# Logic_Engine_-_Rear_LED.net
KiCad netlist of a schematic drawn in EAGLE
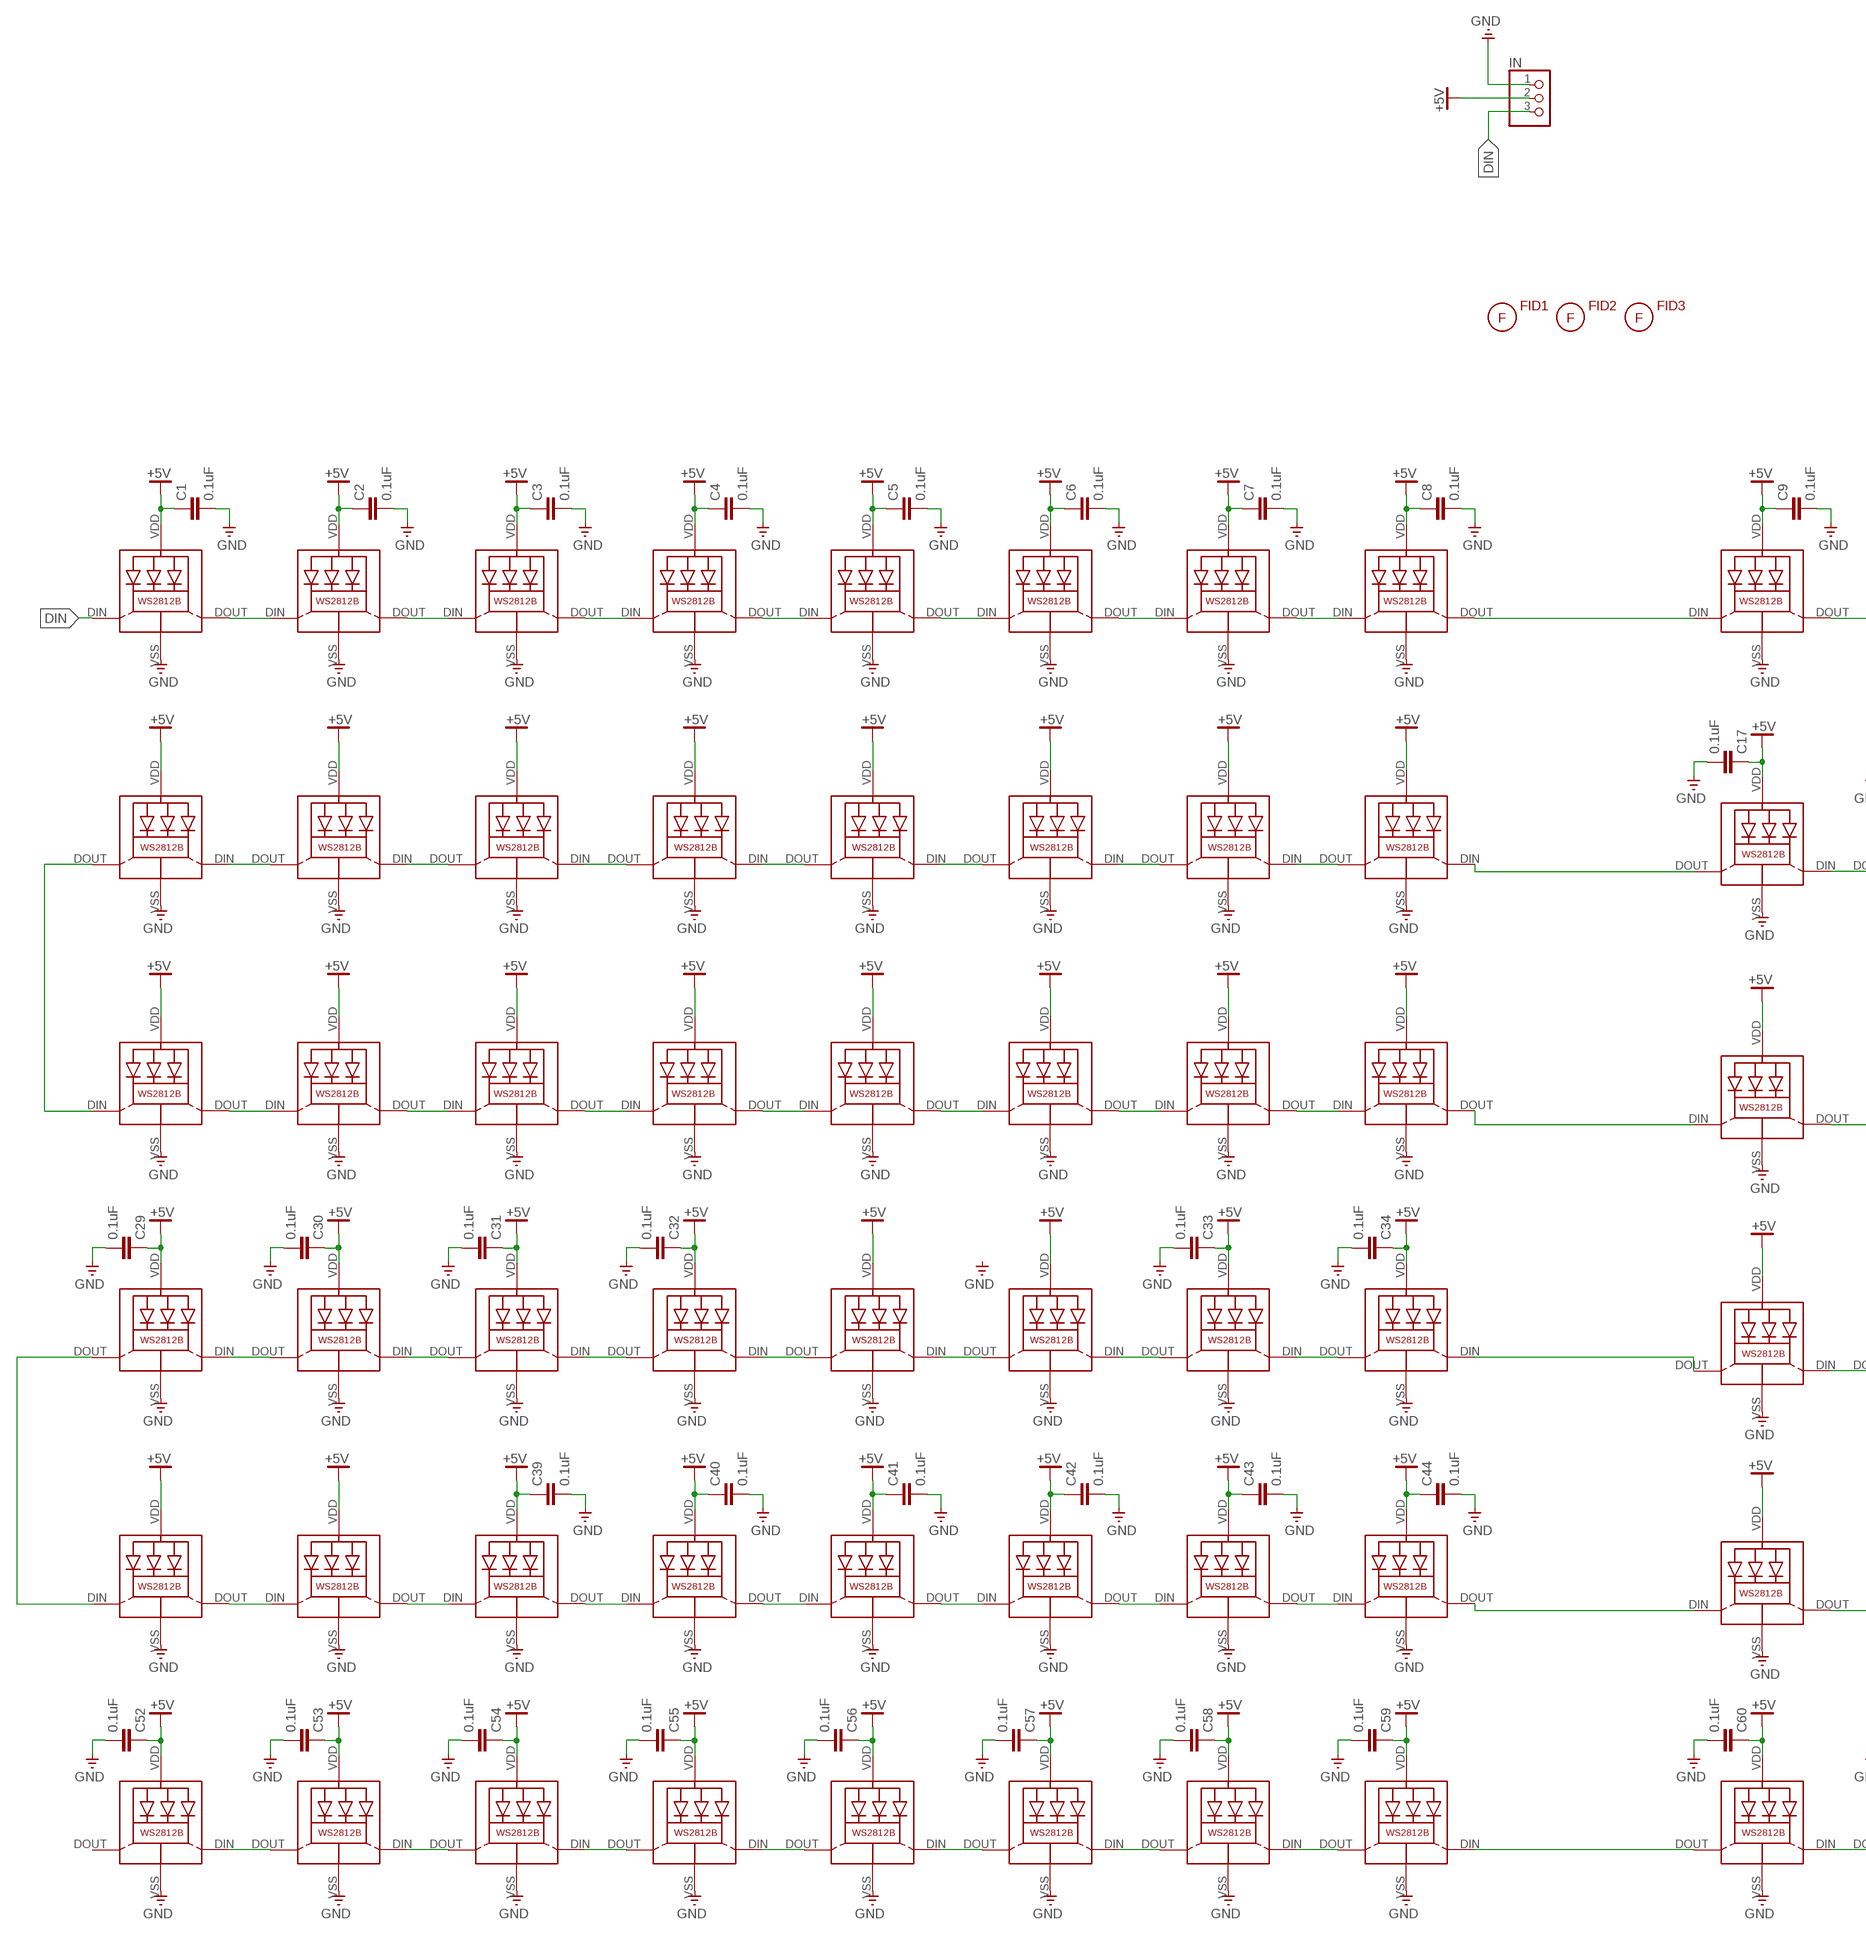
[diagram p0: schematic, sheet 1, part 1 of 2]
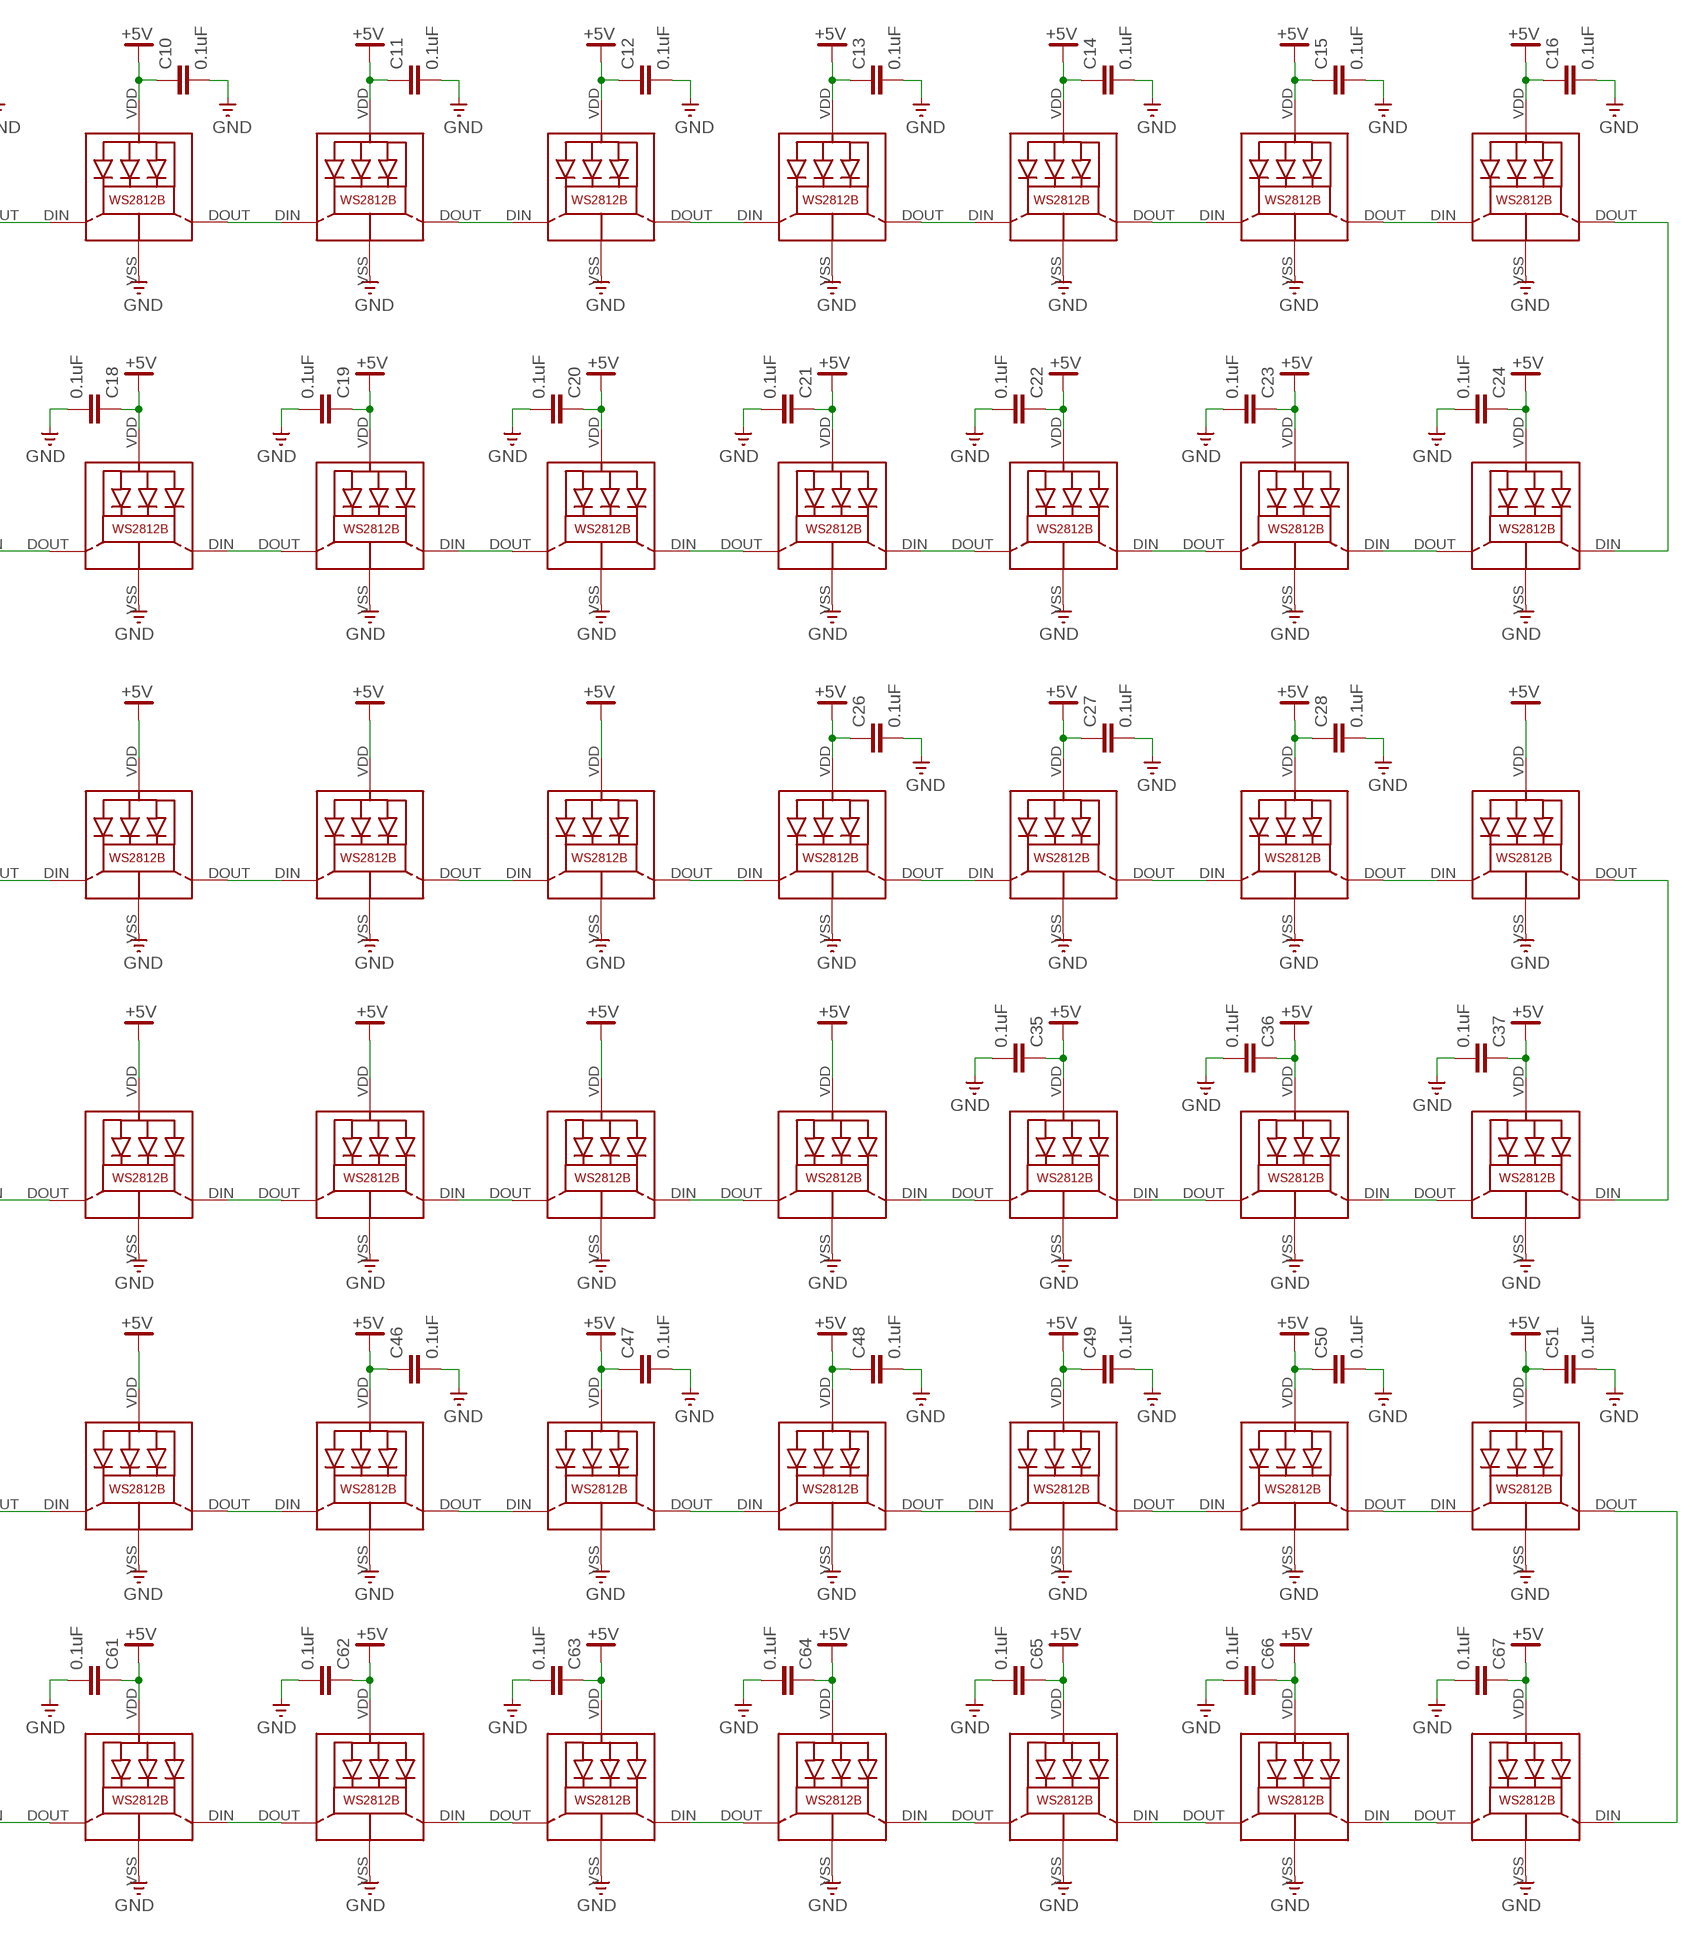
[diagram p1: schematic, sheet 1, part 2 of 2]

(export (version "E")
  (design (tool "Eeschema 10.0.6"))
  (components
    (comp (ref "C1")
      (value "0.1uF")
      (footprint "eagle-import:0603-CAP")
      (libsource (lib "eagle-import") (part "CAP0603-CAP"))
    )
    (comp (ref "C2")
      (value "0.1uF")
      (footprint "eagle-import:0603-CAP")
      (libsource (lib "eagle-import") (part "CAP0603-CAP"))
    )
    (comp (ref "C3")
      (value "0.1uF")
      (footprint "eagle-import:0603-CAP")
      (libsource (lib "eagle-import") (part "CAP0603-CAP"))
    )
    (comp (ref "C4")
      (value "0.1uF")
      (footprint "eagle-import:0603-CAP")
      (libsource (lib "eagle-import") (part "CAP0603-CAP"))
    )
    (comp (ref "C5")
      (value "0.1uF")
      (footprint "eagle-import:0603-CAP")
      (libsource (lib "eagle-import") (part "CAP0603-CAP"))
    )
    (comp (ref "C6")
      (value "0.1uF")
      (footprint "eagle-import:0603-CAP")
      (libsource (lib "eagle-import") (part "CAP0603-CAP"))
    )
    (comp (ref "C7")
      (value "0.1uF")
      (footprint "eagle-import:0603-CAP")
      (libsource (lib "eagle-import") (part "CAP0603-CAP"))
    )
    (comp (ref "C8")
      (value "0.1uF")
      (footprint "eagle-import:0603-CAP")
      (libsource (lib "eagle-import") (part "CAP0603-CAP"))
    )
    (comp (ref "C9")
      (value "0.1uF")
      (footprint "eagle-import:0603-CAP")
      (libsource (lib "eagle-import") (part "CAP0603-CAP"))
    )
    (comp (ref "C10")
      (value "0.1uF")
      (footprint "eagle-import:0603-CAP")
      (libsource (lib "eagle-import") (part "CAP0603-CAP"))
    )
    (comp (ref "C11")
      (value "0.1uF")
      (footprint "eagle-import:0603-CAP")
      (libsource (lib "eagle-import") (part "CAP0603-CAP"))
    )
    (comp (ref "C12")
      (value "0.1uF")
      (footprint "eagle-import:0603-CAP")
      (libsource (lib "eagle-import") (part "CAP0603-CAP"))
    )
    (comp (ref "C13")
      (value "0.1uF")
      (footprint "eagle-import:0603-CAP")
      (libsource (lib "eagle-import") (part "CAP0603-CAP"))
    )
    (comp (ref "C14")
      (value "0.1uF")
      (footprint "eagle-import:0603-CAP")
      (libsource (lib "eagle-import") (part "CAP0603-CAP"))
    )
    (comp (ref "C15")
      (value "0.1uF")
      (footprint "eagle-import:0603-CAP")
      (libsource (lib "eagle-import") (part "CAP0603-CAP"))
    )
    (comp (ref "C16")
      (value "0.1uF")
      (footprint "eagle-import:0603-CAP")
      (libsource (lib "eagle-import") (part "CAP0603-CAP"))
    )
    (comp (ref "C17")
      (value "0.1uF")
      (footprint "eagle-import:0603-CAP")
      (libsource (lib "eagle-import") (part "CAP0603-CAP"))
    )
    (comp (ref "C18")
      (value "0.1uF")
      (footprint "eagle-import:0603-CAP")
      (libsource (lib "eagle-import") (part "CAP0603-CAP"))
    )
    (comp (ref "C19")
      (value "0.1uF")
      (footprint "eagle-import:0603-CAP")
      (libsource (lib "eagle-import") (part "CAP0603-CAP"))
    )
    (comp (ref "C20")
      (value "0.1uF")
      (footprint "eagle-import:0603-CAP")
      (libsource (lib "eagle-import") (part "CAP0603-CAP"))
    )
    (comp (ref "C21")
      (value "0.1uF")
      (footprint "eagle-import:0603-CAP")
      (libsource (lib "eagle-import") (part "CAP0603-CAP"))
    )
    (comp (ref "C22")
      (value "0.1uF")
      (footprint "eagle-import:0603-CAP")
      (libsource (lib "eagle-import") (part "CAP0603-CAP"))
    )
    (comp (ref "C23")
      (value "0.1uF")
      (footprint "eagle-import:0603-CAP")
      (libsource (lib "eagle-import") (part "CAP0603-CAP"))
    )
    (comp (ref "C24")
      (value "0.1uF")
      (footprint "eagle-import:0603-CAP")
      (libsource (lib "eagle-import") (part "CAP0603-CAP"))
    )
    (comp (ref "C26")
      (value "0.1uF")
      (footprint "eagle-import:0603-CAP")
      (libsource (lib "eagle-import") (part "CAP0603-CAP"))
    )
    (comp (ref "C27")
      (value "0.1uF")
      (footprint "eagle-import:0603-CAP")
      (libsource (lib "eagle-import") (part "CAP0603-CAP"))
    )
    (comp (ref "C28")
      (value "0.1uF")
      (footprint "eagle-import:0603-CAP")
      (libsource (lib "eagle-import") (part "CAP0603-CAP"))
    )
    (comp (ref "C29")
      (value "0.1uF")
      (footprint "eagle-import:0603-CAP")
      (libsource (lib "eagle-import") (part "CAP0603-CAP"))
    )
    (comp (ref "C30")
      (value "0.1uF")
      (footprint "eagle-import:0603-CAP")
      (libsource (lib "eagle-import") (part "CAP0603-CAP"))
    )
    (comp (ref "C31")
      (value "0.1uF")
      (footprint "eagle-import:0603-CAP")
      (libsource (lib "eagle-import") (part "CAP0603-CAP"))
    )
    (comp (ref "C32")
      (value "0.1uF")
      (footprint "eagle-import:0603-CAP")
      (libsource (lib "eagle-import") (part "CAP0603-CAP"))
    )
    (comp (ref "C33")
      (value "0.1uF")
      (footprint "eagle-import:0603-CAP")
      (libsource (lib "eagle-import") (part "CAP0603-CAP"))
    )
    (comp (ref "C34")
      (value "0.1uF")
      (footprint "eagle-import:0603-CAP")
      (libsource (lib "eagle-import") (part "CAP0603-CAP"))
    )
    (comp (ref "C35")
      (value "0.1uF")
      (footprint "eagle-import:0603-CAP")
      (libsource (lib "eagle-import") (part "CAP0603-CAP"))
    )
    (comp (ref "C36")
      (value "0.1uF")
      (footprint "eagle-import:0603-CAP")
      (libsource (lib "eagle-import") (part "CAP0603-CAP"))
    )
    (comp (ref "C37")
      (value "0.1uF")
      (footprint "eagle-import:0603-CAP")
      (libsource (lib "eagle-import") (part "CAP0603-CAP"))
    )
    (comp (ref "C39")
      (value "0.1uF")
      (footprint "eagle-import:0603-CAP")
      (libsource (lib "eagle-import") (part "CAP0603-CAP"))
    )
    (comp (ref "C40")
      (value "0.1uF")
      (footprint "eagle-import:0603-CAP")
      (libsource (lib "eagle-import") (part "CAP0603-CAP"))
    )
    (comp (ref "C41")
      (value "0.1uF")
      (footprint "eagle-import:0603-CAP")
      (libsource (lib "eagle-import") (part "CAP0603-CAP"))
    )
    (comp (ref "C42")
      (value "0.1uF")
      (footprint "eagle-import:0603-CAP")
      (libsource (lib "eagle-import") (part "CAP0603-CAP"))
    )
    (comp (ref "C43")
      (value "0.1uF")
      (footprint "eagle-import:0603-CAP")
      (libsource (lib "eagle-import") (part "CAP0603-CAP"))
    )
    (comp (ref "C44")
      (value "0.1uF")
      (footprint "eagle-import:0603-CAP")
      (libsource (lib "eagle-import") (part "CAP0603-CAP"))
    )
    (comp (ref "C46")
      (value "0.1uF")
      (footprint "eagle-import:0603-CAP")
      (libsource (lib "eagle-import") (part "CAP0603-CAP"))
    )
    (comp (ref "C47")
      (value "0.1uF")
      (footprint "eagle-import:0603-CAP")
      (libsource (lib "eagle-import") (part "CAP0603-CAP"))
    )
    (comp (ref "C48")
      (value "0.1uF")
      (footprint "eagle-import:0603-CAP")
      (libsource (lib "eagle-import") (part "CAP0603-CAP"))
    )
    (comp (ref "C49")
      (value "0.1uF")
      (footprint "eagle-import:0603-CAP")
      (libsource (lib "eagle-import") (part "CAP0603-CAP"))
    )
    (comp (ref "C50")
      (value "0.1uF")
      (footprint "eagle-import:0603-CAP")
      (libsource (lib "eagle-import") (part "CAP0603-CAP"))
    )
    (comp (ref "C51")
      (value "0.1uF")
      (footprint "eagle-import:0603-CAP")
      (libsource (lib "eagle-import") (part "CAP0603-CAP"))
    )
    (comp (ref "C52")
      (value "0.1uF")
      (footprint "eagle-import:0603-CAP")
      (libsource (lib "eagle-import") (part "CAP0603-CAP"))
    )
    (comp (ref "C53")
      (value "0.1uF")
      (footprint "eagle-import:0603-CAP")
      (libsource (lib "eagle-import") (part "CAP0603-CAP"))
    )
    (comp (ref "C54")
      (value "0.1uF")
      (footprint "eagle-import:0603-CAP")
      (libsource (lib "eagle-import") (part "CAP0603-CAP"))
    )
    (comp (ref "C55")
      (value "0.1uF")
      (footprint "eagle-import:0603-CAP")
      (libsource (lib "eagle-import") (part "CAP0603-CAP"))
    )
    (comp (ref "C56")
      (value "0.1uF")
      (footprint "eagle-import:0603-CAP")
      (libsource (lib "eagle-import") (part "CAP0603-CAP"))
    )
    (comp (ref "C57")
      (value "0.1uF")
      (footprint "eagle-import:0603-CAP")
      (libsource (lib "eagle-import") (part "CAP0603-CAP"))
    )
    (comp (ref "C58")
      (value "0.1uF")
      (footprint "eagle-import:0603-CAP")
      (libsource (lib "eagle-import") (part "CAP0603-CAP"))
    )
    (comp (ref "C59")
      (value "0.1uF")
      (footprint "eagle-import:0603-CAP")
      (libsource (lib "eagle-import") (part "CAP0603-CAP"))
    )
    (comp (ref "C60")
      (value "0.1uF")
      (footprint "eagle-import:0603-CAP")
      (libsource (lib "eagle-import") (part "CAP0603-CAP"))
    )
    (comp (ref "C61")
      (value "0.1uF")
      (footprint "eagle-import:0603-CAP")
      (libsource (lib "eagle-import") (part "CAP0603-CAP"))
    )
    (comp (ref "C62")
      (value "0.1uF")
      (footprint "eagle-import:0603-CAP")
      (libsource (lib "eagle-import") (part "CAP0603-CAP"))
    )
    (comp (ref "C63")
      (value "0.1uF")
      (footprint "eagle-import:0603-CAP")
      (libsource (lib "eagle-import") (part "CAP0603-CAP"))
    )
    (comp (ref "C64")
      (value "0.1uF")
      (footprint "eagle-import:0603-CAP")
      (libsource (lib "eagle-import") (part "CAP0603-CAP"))
    )
    (comp (ref "C65")
      (value "0.1uF")
      (footprint "eagle-import:0603-CAP")
      (libsource (lib "eagle-import") (part "CAP0603-CAP"))
    )
    (comp (ref "C66")
      (value "0.1uF")
      (footprint "eagle-import:0603-CAP")
      (libsource (lib "eagle-import") (part "CAP0603-CAP"))
    )
    (comp (ref "C67")
      (value "0.1uF")
      (footprint "eagle-import:0603-CAP")
      (libsource (lib "eagle-import") (part "CAP0603-CAP"))
    )
    (comp (ref "FID1")
      (value "FIDUCIAL")
      (footprint "eagle-import:FIDUCIAL_G15")
      (libsource (lib "eagle-import") (part "FIDUCIAL"))
    )
    (comp (ref "FID2")
      (value "FIDUCIAL")
      (footprint "eagle-import:FIDUCIAL_G15")
      (libsource (lib "eagle-import") (part "FIDUCIAL"))
    )
    (comp (ref "FID3")
      (value "FIDUCIAL")
      (footprint "eagle-import:FIDUCIAL_G15")
      (libsource (lib "eagle-import") (part "FIDUCIAL"))
    )
    (comp (ref "IN")
      (value "PINHD-1X3")
      (footprint "eagle-import:1X03")
      (libsource (lib "eagle-import") (part "PINHD-1X3"))
    )
    (comp (ref "L1")
      (value "WS2812B")
      (footprint "eagle-import:WS2812B")
      (libsource (lib "eagle-import") (part "WS2812B"))
    )
    (comp (ref "L2")
      (value "WS2812B")
      (footprint "eagle-import:WS2812B")
      (libsource (lib "eagle-import") (part "WS2812B"))
    )
    (comp (ref "L3")
      (value "WS2812B")
      (footprint "eagle-import:WS2812B")
      (libsource (lib "eagle-import") (part "WS2812B"))
    )
    (comp (ref "L4")
      (value "WS2812B")
      (footprint "eagle-import:WS2812B")
      (libsource (lib "eagle-import") (part "WS2812B"))
    )
    (comp (ref "L5")
      (value "WS2812B")
      (footprint "eagle-import:WS2812B")
      (libsource (lib "eagle-import") (part "WS2812B"))
    )
    (comp (ref "L6")
      (value "WS2812B")
      (footprint "eagle-import:WS2812B")
      (libsource (lib "eagle-import") (part "WS2812B"))
    )
    (comp (ref "L7")
      (value "WS2812B")
      (footprint "eagle-import:WS2812B")
      (libsource (lib "eagle-import") (part "WS2812B"))
    )
    (comp (ref "L8")
      (value "WS2812B")
      (footprint "eagle-import:WS2812B")
      (libsource (lib "eagle-import") (part "WS2812B"))
    )
    (comp (ref "L9")
      (value "WS2812B")
      (footprint "eagle-import:WS2812B")
      (libsource (lib "eagle-import") (part "WS2812B"))
    )
    (comp (ref "L10")
      (value "WS2812B")
      (footprint "eagle-import:WS2812B")
      (libsource (lib "eagle-import") (part "WS2812B"))
    )
    (comp (ref "L11")
      (value "WS2812B")
      (footprint "eagle-import:WS2812B")
      (libsource (lib "eagle-import") (part "WS2812B"))
    )
    (comp (ref "L12")
      (value "WS2812B")
      (footprint "eagle-import:WS2812B")
      (libsource (lib "eagle-import") (part "WS2812B"))
    )
    (comp (ref "L13")
      (value "WS2812B")
      (footprint "eagle-import:WS2812B")
      (libsource (lib "eagle-import") (part "WS2812B"))
    )
    (comp (ref "L14")
      (value "WS2812B")
      (footprint "eagle-import:WS2812B")
      (libsource (lib "eagle-import") (part "WS2812B"))
    )
    (comp (ref "L15")
      (value "WS2812B")
      (footprint "eagle-import:WS2812B")
      (libsource (lib "eagle-import") (part "WS2812B"))
    )
    (comp (ref "L16")
      (value "WS2812B")
      (footprint "eagle-import:WS2812B")
      (libsource (lib "eagle-import") (part "WS2812B"))
    )
    (comp (ref "L17")
      (value "WS2812B")
      (footprint "eagle-import:WS2812B")
      (libsource (lib "eagle-import") (part "WS2812B"))
    )
    (comp (ref "L18")
      (value "WS2812B")
      (footprint "eagle-import:WS2812B")
      (libsource (lib "eagle-import") (part "WS2812B"))
    )
    (comp (ref "L19")
      (value "WS2812B")
      (footprint "eagle-import:WS2812B")
      (libsource (lib "eagle-import") (part "WS2812B"))
    )
    (comp (ref "L20")
      (value "WS2812B")
      (footprint "eagle-import:WS2812B")
      (libsource (lib "eagle-import") (part "WS2812B"))
    )
    (comp (ref "L21")
      (value "WS2812B")
      (footprint "eagle-import:WS2812B")
      (libsource (lib "eagle-import") (part "WS2812B"))
    )
    (comp (ref "L22")
      (value "WS2812B")
      (footprint "eagle-import:WS2812B")
      (libsource (lib "eagle-import") (part "WS2812B"))
    )
    (comp (ref "L23")
      (value "WS2812B")
      (footprint "eagle-import:WS2812B")
      (libsource (lib "eagle-import") (part "WS2812B"))
    )
    (comp (ref "L24")
      (value "WS2812B")
      (footprint "eagle-import:WS2812B")
      (libsource (lib "eagle-import") (part "WS2812B"))
    )
    (comp (ref "L25")
      (value "WS2812B")
      (footprint "eagle-import:WS2812B")
      (libsource (lib "eagle-import") (part "WS2812B"))
    )
    (comp (ref "L26")
      (value "WS2812B")
      (footprint "eagle-import:WS2812B")
      (libsource (lib "eagle-import") (part "WS2812B"))
    )
    (comp (ref "L27")
      (value "WS2812B")
      (footprint "eagle-import:WS2812B")
      (libsource (lib "eagle-import") (part "WS2812B"))
    )
    (comp (ref "L28")
      (value "WS2812B")
      (footprint "eagle-import:WS2812B")
      (libsource (lib "eagle-import") (part "WS2812B"))
    )
    (comp (ref "L29")
      (value "WS2812B")
      (footprint "eagle-import:WS2812B")
      (libsource (lib "eagle-import") (part "WS2812B"))
    )
    (comp (ref "L30")
      (value "WS2812B")
      (footprint "eagle-import:WS2812B")
      (libsource (lib "eagle-import") (part "WS2812B"))
    )
    (comp (ref "L31")
      (value "WS2812B")
      (footprint "eagle-import:WS2812B")
      (libsource (lib "eagle-import") (part "WS2812B"))
    )
    (comp (ref "L32")
      (value "WS2812B")
      (footprint "eagle-import:WS2812B")
      (libsource (lib "eagle-import") (part "WS2812B"))
    )
    (comp (ref "L33")
      (value "WS2812B")
      (footprint "eagle-import:WS2812B")
      (libsource (lib "eagle-import") (part "WS2812B"))
    )
    (comp (ref "L34")
      (value "WS2812B")
      (footprint "eagle-import:WS2812B")
      (libsource (lib "eagle-import") (part "WS2812B"))
    )
    (comp (ref "L35")
      (value "WS2812B")
      (footprint "eagle-import:WS2812B")
      (libsource (lib "eagle-import") (part "WS2812B"))
    )
    (comp (ref "L36")
      (value "WS2812B")
      (footprint "eagle-import:WS2812B")
      (libsource (lib "eagle-import") (part "WS2812B"))
    )
    (comp (ref "L37")
      (value "WS2812B")
      (footprint "eagle-import:WS2812B")
      (libsource (lib "eagle-import") (part "WS2812B"))
    )
    (comp (ref "L38")
      (value "WS2812B")
      (footprint "eagle-import:WS2812B")
      (libsource (lib "eagle-import") (part "WS2812B"))
    )
    (comp (ref "L39")
      (value "WS2812B")
      (footprint "eagle-import:WS2812B")
      (libsource (lib "eagle-import") (part "WS2812B"))
    )
    (comp (ref "L40")
      (value "WS2812B")
      (footprint "eagle-import:WS2812B")
      (libsource (lib "eagle-import") (part "WS2812B"))
    )
    (comp (ref "L41")
      (value "WS2812B")
      (footprint "eagle-import:WS2812B")
      (libsource (lib "eagle-import") (part "WS2812B"))
    )
    (comp (ref "L42")
      (value "WS2812B")
      (footprint "eagle-import:WS2812B")
      (libsource (lib "eagle-import") (part "WS2812B"))
    )
    (comp (ref "L43")
      (value "WS2812B")
      (footprint "eagle-import:WS2812B")
      (libsource (lib "eagle-import") (part "WS2812B"))
    )
    (comp (ref "L44")
      (value "WS2812B")
      (footprint "eagle-import:WS2812B")
      (libsource (lib "eagle-import") (part "WS2812B"))
    )
    (comp (ref "L45")
      (value "WS2812B")
      (footprint "eagle-import:WS2812B")
      (libsource (lib "eagle-import") (part "WS2812B"))
    )
    (comp (ref "L46")
      (value "WS2812B")
      (footprint "eagle-import:WS2812B")
      (libsource (lib "eagle-import") (part "WS2812B"))
    )
    (comp (ref "L47")
      (value "WS2812B")
      (footprint "eagle-import:WS2812B")
      (libsource (lib "eagle-import") (part "WS2812B"))
    )
    (comp (ref "L48")
      (value "WS2812B")
      (footprint "eagle-import:WS2812B")
      (libsource (lib "eagle-import") (part "WS2812B"))
    )
    (comp (ref "L49")
      (value "WS2812B")
      (footprint "eagle-import:WS2812B")
      (libsource (lib "eagle-import") (part "WS2812B"))
    )
    (comp (ref "L50")
      (value "WS2812B")
      (footprint "eagle-import:WS2812B")
      (libsource (lib "eagle-import") (part "WS2812B"))
    )
    (comp (ref "L51")
      (value "WS2812B")
      (footprint "eagle-import:WS2812B")
      (libsource (lib "eagle-import") (part "WS2812B"))
    )
    (comp (ref "L52")
      (value "WS2812B")
      (footprint "eagle-import:WS2812B")
      (libsource (lib "eagle-import") (part "WS2812B"))
    )
    (comp (ref "L53")
      (value "WS2812B")
      (footprint "eagle-import:WS2812B")
      (libsource (lib "eagle-import") (part "WS2812B"))
    )
    (comp (ref "L54")
      (value "WS2812B")
      (footprint "eagle-import:WS2812B")
      (libsource (lib "eagle-import") (part "WS2812B"))
    )
    (comp (ref "L55")
      (value "WS2812B")
      (footprint "eagle-import:WS2812B")
      (libsource (lib "eagle-import") (part "WS2812B"))
    )
    (comp (ref "L56")
      (value "WS2812B")
      (footprint "eagle-import:WS2812B")
      (libsource (lib "eagle-import") (part "WS2812B"))
    )
    (comp (ref "L57")
      (value "WS2812B")
      (footprint "eagle-import:WS2812B")
      (libsource (lib "eagle-import") (part "WS2812B"))
    )
    (comp (ref "L58")
      (value "WS2812B")
      (footprint "eagle-import:WS2812B")
      (libsource (lib "eagle-import") (part "WS2812B"))
    )
    (comp (ref "L59")
      (value "WS2812B")
      (footprint "eagle-import:WS2812B")
      (libsource (lib "eagle-import") (part "WS2812B"))
    )
    (comp (ref "L60")
      (value "WS2812B")
      (footprint "eagle-import:WS2812B")
      (libsource (lib "eagle-import") (part "WS2812B"))
    )
    (comp (ref "L61")
      (value "WS2812B")
      (footprint "eagle-import:WS2812B")
      (libsource (lib "eagle-import") (part "WS2812B"))
    )
    (comp (ref "L62")
      (value "WS2812B")
      (footprint "eagle-import:WS2812B")
      (libsource (lib "eagle-import") (part "WS2812B"))
    )
    (comp (ref "L63")
      (value "WS2812B")
      (footprint "eagle-import:WS2812B")
      (libsource (lib "eagle-import") (part "WS2812B"))
    )
    (comp (ref "L64")
      (value "WS2812B")
      (footprint "eagle-import:WS2812B")
      (libsource (lib "eagle-import") (part "WS2812B"))
    )
    (comp (ref "L65")
      (value "WS2812B")
      (footprint "eagle-import:WS2812B")
      (libsource (lib "eagle-import") (part "WS2812B"))
    )
    (comp (ref "L66")
      (value "WS2812B")
      (footprint "eagle-import:WS2812B")
      (libsource (lib "eagle-import") (part "WS2812B"))
    )
    (comp (ref "L67")
      (value "WS2812B")
      (footprint "eagle-import:WS2812B")
      (libsource (lib "eagle-import") (part "WS2812B"))
    )
    (comp (ref "L68")
      (value "WS2812B")
      (footprint "eagle-import:WS2812B")
      (libsource (lib "eagle-import") (part "WS2812B"))
    )
    (comp (ref "L69")
      (value "WS2812B")
      (footprint "eagle-import:WS2812B")
      (libsource (lib "eagle-import") (part "WS2812B"))
    )
    (comp (ref "L70")
      (value "WS2812B")
      (footprint "eagle-import:WS2812B")
      (libsource (lib "eagle-import") (part "WS2812B"))
    )
    (comp (ref "L71")
      (value "WS2812B")
      (footprint "eagle-import:WS2812B")
      (libsource (lib "eagle-import") (part "WS2812B"))
    )
    (comp (ref "L72")
      (value "WS2812B")
      (footprint "eagle-import:WS2812B")
      (libsource (lib "eagle-import") (part "WS2812B"))
    )
    (comp (ref "L73")
      (value "WS2812B")
      (footprint "eagle-import:WS2812B")
      (libsource (lib "eagle-import") (part "WS2812B"))
    )
    (comp (ref "L74")
      (value "WS2812B")
      (footprint "eagle-import:WS2812B")
      (libsource (lib "eagle-import") (part "WS2812B"))
    )
    (comp (ref "L75")
      (value "WS2812B")
      (footprint "eagle-import:WS2812B")
      (libsource (lib "eagle-import") (part "WS2812B"))
    )
    (comp (ref "L76")
      (value "WS2812B")
      (footprint "eagle-import:WS2812B")
      (libsource (lib "eagle-import") (part "WS2812B"))
    )
    (comp (ref "L77")
      (value "WS2812B")
      (footprint "eagle-import:WS2812B")
      (libsource (lib "eagle-import") (part "WS2812B"))
    )
    (comp (ref "L78")
      (value "WS2812B")
      (footprint "eagle-import:WS2812B")
      (libsource (lib "eagle-import") (part "WS2812B"))
    )
    (comp (ref "L79")
      (value "WS2812B")
      (footprint "eagle-import:WS2812B")
      (libsource (lib "eagle-import") (part "WS2812B"))
    )
    (comp (ref "L80")
      (value "WS2812B")
      (footprint "eagle-import:WS2812B")
      (libsource (lib "eagle-import") (part "WS2812B"))
    )
    (comp (ref "L81")
      (value "WS2812B")
      (footprint "eagle-import:WS2812B")
      (libsource (lib "eagle-import") (part "WS2812B"))
    )
    (comp (ref "L82")
      (value "WS2812B")
      (footprint "eagle-import:WS2812B")
      (libsource (lib "eagle-import") (part "WS2812B"))
    )
    (comp (ref "L83")
      (value "WS2812B")
      (footprint "eagle-import:WS2812B")
      (libsource (lib "eagle-import") (part "WS2812B"))
    )
    (comp (ref "L84")
      (value "WS2812B")
      (footprint "eagle-import:WS2812B")
      (libsource (lib "eagle-import") (part "WS2812B"))
    )
    (comp (ref "L85")
      (value "WS2812B")
      (footprint "eagle-import:WS2812B")
      (libsource (lib "eagle-import") (part "WS2812B"))
    )
    (comp (ref "L86")
      (value "WS2812B")
      (footprint "eagle-import:WS2812B")
      (libsource (lib "eagle-import") (part "WS2812B"))
    )
    (comp (ref "L87")
      (value "WS2812B")
      (footprint "eagle-import:WS2812B")
      (libsource (lib "eagle-import") (part "WS2812B"))
    )
    (comp (ref "L88")
      (value "WS2812B")
      (footprint "eagle-import:WS2812B")
      (libsource (lib "eagle-import") (part "WS2812B"))
    )
    (comp (ref "L89")
      (value "WS2812B")
      (footprint "eagle-import:WS2812B")
      (libsource (lib "eagle-import") (part "WS2812B"))
    )
    (comp (ref "L90")
      (value "WS2812B")
      (footprint "eagle-import:WS2812B")
      (libsource (lib "eagle-import") (part "WS2812B"))
    )
    (comp (ref "L91")
      (value "WS2812B")
      (footprint "eagle-import:WS2812B")
      (libsource (lib "eagle-import") (part "WS2812B"))
    )
    (comp (ref "L92")
      (value "WS2812B")
      (footprint "eagle-import:WS2812B")
      (libsource (lib "eagle-import") (part "WS2812B"))
    )
    (comp (ref "L93")
      (value "WS2812B")
      (footprint "eagle-import:WS2812B")
      (libsource (lib "eagle-import") (part "WS2812B"))
    )
    (comp (ref "L94")
      (value "WS2812B")
      (footprint "eagle-import:WS2812B")
      (libsource (lib "eagle-import") (part "WS2812B"))
    )
    (comp (ref "L95")
      (value "WS2812B")
      (footprint "eagle-import:WS2812B")
      (libsource (lib "eagle-import") (part "WS2812B"))
    )
    (comp (ref "L96")
      (value "WS2812B")
      (footprint "eagle-import:WS2812B")
      (libsource (lib "eagle-import") (part "WS2812B"))
    )
  )
  (nets
    (net (code "1") (name "+5V") (class "Default")
      (node (ref "C1") (pin "1") (pinfunction "1_1") (pintype "passive"))
      (node (ref "C10") (pin "1") (pinfunction "1_1") (pintype "passive"))
      (node (ref "C11") (pin "1") (pinfunction "1_1") (pintype "passive"))
      (node (ref "C12") (pin "1") (pinfunction "1_1") (pintype "passive"))
      (node (ref "C13") (pin "1") (pinfunction "1_1") (pintype "passive"))
      (node (ref "C14") (pin "1") (pinfunction "1_1") (pintype "passive"))
      (node (ref "C15") (pin "1") (pinfunction "1_1") (pintype "passive"))
      (node (ref "C16") (pin "1") (pinfunction "1_1") (pintype "passive"))
      (node (ref "C17") (pin "1") (pinfunction "1_1") (pintype "passive"))
      (node (ref "C18") (pin "1") (pinfunction "1_1") (pintype "passive"))
      (node (ref "C19") (pin "1") (pinfunction "1_1") (pintype "passive"))
      (node (ref "C2") (pin "1") (pinfunction "1_1") (pintype "passive"))
      (node (ref "C20") (pin "1") (pinfunction "1_1") (pintype "passive"))
      (node (ref "C21") (pin "1") (pinfunction "1_1") (pintype "passive"))
      (node (ref "C22") (pin "1") (pinfunction "1_1") (pintype "passive"))
      (node (ref "C23") (pin "1") (pinfunction "1_1") (pintype "passive"))
      (node (ref "C24") (pin "1") (pinfunction "1_1") (pintype "passive"))
      (node (ref "C26") (pin "1") (pinfunction "1_1") (pintype "passive"))
      (node (ref "C27") (pin "1") (pinfunction "1_1") (pintype "passive"))
      (node (ref "C28") (pin "1") (pinfunction "1_1") (pintype "passive"))
      (node (ref "C29") (pin "1") (pinfunction "1_1") (pintype "passive"))
      (node (ref "C3") (pin "1") (pinfunction "1_1") (pintype "passive"))
      (node (ref "C30") (pin "1") (pinfunction "1_1") (pintype "passive"))
      (node (ref "C31") (pin "1") (pinfunction "1_1") (pintype "passive"))
      (node (ref "C32") (pin "1") (pinfunction "1_1") (pintype "passive"))
      (node (ref "C33") (pin "1") (pinfunction "1_1") (pintype "passive"))
      (node (ref "C34") (pin "1") (pinfunction "1_1") (pintype "passive"))
      (node (ref "C35") (pin "1") (pinfunction "1_1") (pintype "passive"))
      (node (ref "C36") (pin "1") (pinfunction "1_1") (pintype "passive"))
      (node (ref "C37") (pin "1") (pinfunction "1_1") (pintype "passive"))
      (node (ref "C39") (pin "1") (pinfunction "1_1") (pintype "passive"))
      (node (ref "C4") (pin "1") (pinfunction "1_1") (pintype "passive"))
      (node (ref "C40") (pin "1") (pinfunction "1_1") (pintype "passive"))
      (node (ref "C41") (pin "1") (pinfunction "1_1") (pintype "passive"))
      (node (ref "C42") (pin "1") (pinfunction "1_1") (pintype "passive"))
      (node (ref "C43") (pin "1") (pinfunction "1_1") (pintype "passive"))
      (node (ref "C44") (pin "1") (pinfunction "1_1") (pintype "passive"))
      (node (ref "C46") (pin "1") (pinfunction "1_1") (pintype "passive"))
      (node (ref "C47") (pin "1") (pinfunction "1_1") (pintype "passive"))
      (node (ref "C48") (pin "1") (pinfunction "1_1") (pintype "passive"))
      (node (ref "C49") (pin "1") (pinfunction "1_1") (pintype "passive"))
      (node (ref "C5") (pin "1") (pinfunction "1_1") (pintype "passive"))
      (node (ref "C50") (pin "1") (pinfunction "1_1") (pintype "passive"))
      (node (ref "C51") (pin "1") (pinfunction "1_1") (pintype "passive"))
      (node (ref "C52") (pin "1") (pinfunction "1_1") (pintype "passive"))
      (node (ref "C53") (pin "1") (pinfunction "1_1") (pintype "passive"))
      (node (ref "C54") (pin "1") (pinfunction "1_1") (pintype "passive"))
      (node (ref "C55") (pin "1") (pinfunction "1_1") (pintype "passive"))
      (node (ref "C56") (pin "1") (pinfunction "1_1") (pintype "passive"))
      (node (ref "C57") (pin "1") (pinfunction "1_1") (pintype "passive"))
      (node (ref "C58") (pin "1") (pinfunction "1_1") (pintype "passive"))
      (node (ref "C59") (pin "1") (pinfunction "1_1") (pintype "passive"))
      (node (ref "C6") (pin "1") (pinfunction "1_1") (pintype "passive"))
      (node (ref "C60") (pin "1") (pinfunction "1_1") (pintype "passive"))
      (node (ref "C61") (pin "1") (pinfunction "1_1") (pintype "passive"))
      (node (ref "C62") (pin "1") (pinfunction "1_1") (pintype "passive"))
      (node (ref "C63") (pin "1") (pinfunction "1_1") (pintype "passive"))
      (node (ref "C64") (pin "1") (pinfunction "1_1") (pintype "passive"))
      (node (ref "C65") (pin "1") (pinfunction "1_1") (pintype "passive"))
      (node (ref "C66") (pin "1") (pinfunction "1_1") (pintype "passive"))
      (node (ref "C67") (pin "1") (pinfunction "1_1") (pintype "passive"))
      (node (ref "C7") (pin "1") (pinfunction "1_1") (pintype "passive"))
      (node (ref "C8") (pin "1") (pinfunction "1_1") (pintype "passive"))
      (node (ref "C9") (pin "1") (pinfunction "1_1") (pintype "passive"))
      (node (ref "IN") (pin "2") (pinfunction "2_2") (pintype "passive"))
      (node (ref "L1") (pin "VDD") (pinfunction "VDD_VDD") (pintype "power_in"))
      (node (ref "L10") (pin "VDD") (pinfunction "VDD_VDD") (pintype "power_in"))
      (node (ref "L11") (pin "VDD") (pinfunction "VDD_VDD") (pintype "power_in"))
      (node (ref "L12") (pin "VDD") (pinfunction "VDD_VDD") (pintype "power_in"))
      (node (ref "L13") (pin "VDD") (pinfunction "VDD_VDD") (pintype "power_in"))
      (node (ref "L14") (pin "VDD") (pinfunction "VDD_VDD") (pintype "power_in"))
      (node (ref "L15") (pin "VDD") (pinfunction "VDD_VDD") (pintype "power_in"))
      (node (ref "L16") (pin "VDD") (pinfunction "VDD_VDD") (pintype "power_in"))
      (node (ref "L17") (pin "VDD") (pinfunction "VDD_VDD") (pintype "power_in"))
      (node (ref "L18") (pin "VDD") (pinfunction "VDD_VDD") (pintype "power_in"))
      (node (ref "L19") (pin "VDD") (pinfunction "VDD_VDD") (pintype "power_in"))
      (node (ref "L2") (pin "VDD") (pinfunction "VDD_VDD") (pintype "power_in"))
      (node (ref "L20") (pin "VDD") (pinfunction "VDD_VDD") (pintype "power_in"))
      (node (ref "L21") (pin "VDD") (pinfunction "VDD_VDD") (pintype "power_in"))
      (node (ref "L22") (pin "VDD") (pinfunction "VDD_VDD") (pintype "power_in"))
      (node (ref "L23") (pin "VDD") (pinfunction "VDD_VDD") (pintype "power_in"))
      (node (ref "L24") (pin "VDD") (pinfunction "VDD_VDD") (pintype "power_in"))
      (node (ref "L25") (pin "VDD") (pinfunction "VDD_VDD") (pintype "power_in"))
      (node (ref "L26") (pin "VDD") (pinfunction "VDD_VDD") (pintype "power_in"))
      (node (ref "L27") (pin "VDD") (pinfunction "VDD_VDD") (pintype "power_in"))
      (node (ref "L28") (pin "VDD") (pinfunction "VDD_VDD") (pintype "power_in"))
      (node (ref "L29") (pin "VDD") (pinfunction "VDD_VDD") (pintype "power_in"))
      (node (ref "L3") (pin "VDD") (pinfunction "VDD_VDD") (pintype "power_in"))
      (node (ref "L30") (pin "VDD") (pinfunction "VDD_VDD") (pintype "power_in"))
      (node (ref "L31") (pin "VDD") (pinfunction "VDD_VDD") (pintype "power_in"))
      (node (ref "L32") (pin "VDD") (pinfunction "VDD_VDD") (pintype "power_in"))
      (node (ref "L33") (pin "VDD") (pinfunction "VDD_VDD") (pintype "power_in"))
      (node (ref "L34") (pin "VDD") (pinfunction "VDD_VDD") (pintype "power_in"))
      (node (ref "L35") (pin "VDD") (pinfunction "VDD_VDD") (pintype "power_in"))
      (node (ref "L36") (pin "VDD") (pinfunction "VDD_VDD") (pintype "power_in"))
      (node (ref "L37") (pin "VDD") (pinfunction "VDD_VDD") (pintype "power_in"))
      (node (ref "L38") (pin "VDD") (pinfunction "VDD_VDD") (pintype "power_in"))
      (node (ref "L39") (pin "VDD") (pinfunction "VDD_VDD") (pintype "power_in"))
      (node (ref "L4") (pin "VDD") (pinfunction "VDD_VDD") (pintype "power_in"))
      (node (ref "L40") (pin "VDD") (pinfunction "VDD_VDD") (pintype "power_in"))
      (node (ref "L41") (pin "VDD") (pinfunction "VDD_VDD") (pintype "power_in"))
      (node (ref "L42") (pin "VDD") (pinfunction "VDD_VDD") (pintype "power_in"))
      (node (ref "L43") (pin "VDD") (pinfunction "VDD_VDD") (pintype "power_in"))
      (node (ref "L44") (pin "VDD") (pinfunction "VDD_VDD") (pintype "power_in"))
      (node (ref "L45") (pin "VDD") (pinfunction "VDD_VDD") (pintype "power_in"))
      (node (ref "L46") (pin "VDD") (pinfunction "VDD_VDD") (pintype "power_in"))
      (node (ref "L47") (pin "VDD") (pinfunction "VDD_VDD") (pintype "power_in"))
      (node (ref "L48") (pin "VDD") (pinfunction "VDD_VDD") (pintype "power_in"))
      (node (ref "L49") (pin "VDD") (pinfunction "VDD_VDD") (pintype "power_in"))
      (node (ref "L5") (pin "VDD") (pinfunction "VDD_VDD") (pintype "power_in"))
      (node (ref "L50") (pin "VDD") (pinfunction "VDD_VDD") (pintype "power_in"))
      (node (ref "L51") (pin "VDD") (pinfunction "VDD_VDD") (pintype "power_in"))
      (node (ref "L52") (pin "VDD") (pinfunction "VDD_VDD") (pintype "power_in"))
      (node (ref "L53") (pin "VDD") (pinfunction "VDD_VDD") (pintype "power_in"))
      (node (ref "L54") (pin "VDD") (pinfunction "VDD_VDD") (pintype "power_in"))
      (node (ref "L55") (pin "VDD") (pinfunction "VDD_VDD") (pintype "power_in"))
      (node (ref "L56") (pin "VDD") (pinfunction "VDD_VDD") (pintype "power_in"))
      (node (ref "L57") (pin "VDD") (pinfunction "VDD_VDD") (pintype "power_in"))
      (node (ref "L58") (pin "VDD") (pinfunction "VDD_VDD") (pintype "power_in"))
      (node (ref "L59") (pin "VDD") (pinfunction "VDD_VDD") (pintype "power_in"))
      (node (ref "L6") (pin "VDD") (pinfunction "VDD_VDD") (pintype "power_in"))
      (node (ref "L60") (pin "VDD") (pinfunction "VDD_VDD") (pintype "power_in"))
      (node (ref "L61") (pin "VDD") (pinfunction "VDD_VDD") (pintype "power_in"))
      (node (ref "L62") (pin "VDD") (pinfunction "VDD_VDD") (pintype "power_in"))
      (node (ref "L63") (pin "VDD") (pinfunction "VDD_VDD") (pintype "power_in"))
      (node (ref "L64") (pin "VDD") (pinfunction "VDD_VDD") (pintype "power_in"))
      (node (ref "L65") (pin "VDD") (pinfunction "VDD_VDD") (pintype "power_in"))
      (node (ref "L66") (pin "VDD") (pinfunction "VDD_VDD") (pintype "power_in"))
      (node (ref "L67") (pin "VDD") (pinfunction "VDD_VDD") (pintype "power_in"))
      (node (ref "L68") (pin "VDD") (pinfunction "VDD_VDD") (pintype "power_in"))
      (node (ref "L69") (pin "VDD") (pinfunction "VDD_VDD") (pintype "power_in"))
      (node (ref "L7") (pin "VDD") (pinfunction "VDD_VDD") (pintype "power_in"))
      (node (ref "L70") (pin "VDD") (pinfunction "VDD_VDD") (pintype "power_in"))
      (node (ref "L71") (pin "VDD") (pinfunction "VDD_VDD") (pintype "power_in"))
      (node (ref "L72") (pin "VDD") (pinfunction "VDD_VDD") (pintype "power_in"))
      (node (ref "L73") (pin "VDD") (pinfunction "VDD_VDD") (pintype "power_in"))
      (node (ref "L74") (pin "VDD") (pinfunction "VDD_VDD") (pintype "power_in"))
      (node (ref "L75") (pin "VDD") (pinfunction "VDD_VDD") (pintype "power_in"))
      (node (ref "L76") (pin "VDD") (pinfunction "VDD_VDD") (pintype "power_in"))
      (node (ref "L77") (pin "VDD") (pinfunction "VDD_VDD") (pintype "power_in"))
      (node (ref "L78") (pin "VDD") (pinfunction "VDD_VDD") (pintype "power_in"))
      (node (ref "L79") (pin "VDD") (pinfunction "VDD_VDD") (pintype "power_in"))
      (node (ref "L8") (pin "VDD") (pinfunction "VDD_VDD") (pintype "power_in"))
      (node (ref "L80") (pin "VDD") (pinfunction "VDD_VDD") (pintype "power_in"))
      (node (ref "L81") (pin "VDD") (pinfunction "VDD_VDD") (pintype "power_in"))
      (node (ref "L82") (pin "VDD") (pinfunction "VDD_VDD") (pintype "power_in"))
      (node (ref "L83") (pin "VDD") (pinfunction "VDD_VDD") (pintype "power_in"))
      (node (ref "L84") (pin "VDD") (pinfunction "VDD_VDD") (pintype "power_in"))
      (node (ref "L85") (pin "VDD") (pinfunction "VDD_VDD") (pintype "power_in"))
      (node (ref "L86") (pin "VDD") (pinfunction "VDD_VDD") (pintype "power_in"))
      (node (ref "L87") (pin "VDD") (pinfunction "VDD_VDD") (pintype "power_in"))
      (node (ref "L88") (pin "VDD") (pinfunction "VDD_VDD") (pintype "power_in"))
      (node (ref "L89") (pin "VDD") (pinfunction "VDD_VDD") (pintype "power_in"))
      (node (ref "L9") (pin "VDD") (pinfunction "VDD_VDD") (pintype "power_in"))
      (node (ref "L90") (pin "VDD") (pinfunction "VDD_VDD") (pintype "power_in"))
      (node (ref "L91") (pin "VDD") (pinfunction "VDD_VDD") (pintype "power_in"))
      (node (ref "L92") (pin "VDD") (pinfunction "VDD_VDD") (pintype "power_in"))
      (node (ref "L93") (pin "VDD") (pinfunction "VDD_VDD") (pintype "power_in"))
      (node (ref "L94") (pin "VDD") (pinfunction "VDD_VDD") (pintype "power_in"))
      (node (ref "L95") (pin "VDD") (pinfunction "VDD_VDD") (pintype "power_in"))
      (node (ref "L96") (pin "VDD") (pinfunction "VDD_VDD") (pintype "power_in"))
    )
    (net (code "2") (name "DIN") (class "Default")
      (node (ref "IN") (pin "3") (pinfunction "3_3") (pintype "passive"))
      (node (ref "L1") (pin "DIN") (pinfunction "DI_DIN") (pintype "input"))
    )
    (net (code "3") (name "GND") (class "Default")
      (node (ref "C1") (pin "2") (pinfunction "2_2") (pintype "passive"))
      (node (ref "C10") (pin "2") (pinfunction "2_2") (pintype "passive"))
      (node (ref "C11") (pin "2") (pinfunction "2_2") (pintype "passive"))
      (node (ref "C12") (pin "2") (pinfunction "2_2") (pintype "passive"))
      (node (ref "C13") (pin "2") (pinfunction "2_2") (pintype "passive"))
      (node (ref "C14") (pin "2") (pinfunction "2_2") (pintype "passive"))
      (node (ref "C15") (pin "2") (pinfunction "2_2") (pintype "passive"))
      (node (ref "C16") (pin "2") (pinfunction "2_2") (pintype "passive"))
      (node (ref "C17") (pin "2") (pinfunction "2_2") (pintype "passive"))
      (node (ref "C18") (pin "2") (pinfunction "2_2") (pintype "passive"))
      (node (ref "C19") (pin "2") (pinfunction "2_2") (pintype "passive"))
      (node (ref "C2") (pin "2") (pinfunction "2_2") (pintype "passive"))
      (node (ref "C20") (pin "2") (pinfunction "2_2") (pintype "passive"))
      (node (ref "C21") (pin "2") (pinfunction "2_2") (pintype "passive"))
      (node (ref "C22") (pin "2") (pinfunction "2_2") (pintype "passive"))
      (node (ref "C23") (pin "2") (pinfunction "2_2") (pintype "passive"))
      (node (ref "C24") (pin "2") (pinfunction "2_2") (pintype "passive"))
      (node (ref "C26") (pin "2") (pinfunction "2_2") (pintype "passive"))
      (node (ref "C27") (pin "2") (pinfunction "2_2") (pintype "passive"))
      (node (ref "C28") (pin "2") (pinfunction "2_2") (pintype "passive"))
      (node (ref "C29") (pin "2") (pinfunction "2_2") (pintype "passive"))
      (node (ref "C3") (pin "2") (pinfunction "2_2") (pintype "passive"))
      (node (ref "C30") (pin "2") (pinfunction "2_2") (pintype "passive"))
      (node (ref "C31") (pin "2") (pinfunction "2_2") (pintype "passive"))
      (node (ref "C32") (pin "2") (pinfunction "2_2") (pintype "passive"))
      (node (ref "C33") (pin "2") (pinfunction "2_2") (pintype "passive"))
      (node (ref "C34") (pin "2") (pinfunction "2_2") (pintype "passive"))
      (node (ref "C35") (pin "2") (pinfunction "2_2") (pintype "passive"))
      (node (ref "C36") (pin "2") (pinfunction "2_2") (pintype "passive"))
      (node (ref "C37") (pin "2") (pinfunction "2_2") (pintype "passive"))
      (node (ref "C39") (pin "2") (pinfunction "2_2") (pintype "passive"))
      (node (ref "C4") (pin "2") (pinfunction "2_2") (pintype "passive"))
      (node (ref "C40") (pin "2") (pinfunction "2_2") (pintype "passive"))
      (node (ref "C41") (pin "2") (pinfunction "2_2") (pintype "passive"))
      (node (ref "C42") (pin "2") (pinfunction "2_2") (pintype "passive"))
      (node (ref "C43") (pin "2") (pinfunction "2_2") (pintype "passive"))
      (node (ref "C44") (pin "2") (pinfunction "2_2") (pintype "passive"))
      (node (ref "C46") (pin "2") (pinfunction "2_2") (pintype "passive"))
      (node (ref "C47") (pin "2") (pinfunction "2_2") (pintype "passive"))
      (node (ref "C48") (pin "2") (pinfunction "2_2") (pintype "passive"))
      (node (ref "C49") (pin "2") (pinfunction "2_2") (pintype "passive"))
      (node (ref "C5") (pin "2") (pinfunction "2_2") (pintype "passive"))
      (node (ref "C50") (pin "2") (pinfunction "2_2") (pintype "passive"))
      (node (ref "C51") (pin "2") (pinfunction "2_2") (pintype "passive"))
      (node (ref "C52") (pin "2") (pinfunction "2_2") (pintype "passive"))
      (node (ref "C53") (pin "2") (pinfunction "2_2") (pintype "passive"))
      (node (ref "C54") (pin "2") (pinfunction "2_2") (pintype "passive"))
      (node (ref "C55") (pin "2") (pinfunction "2_2") (pintype "passive"))
      (node (ref "C56") (pin "2") (pinfunction "2_2") (pintype "passive"))
      (node (ref "C57") (pin "2") (pinfunction "2_2") (pintype "passive"))
      (node (ref "C58") (pin "2") (pinfunction "2_2") (pintype "passive"))
      (node (ref "C59") (pin "2") (pinfunction "2_2") (pintype "passive"))
      (node (ref "C6") (pin "2") (pinfunction "2_2") (pintype "passive"))
      (node (ref "C60") (pin "2") (pinfunction "2_2") (pintype "passive"))
      (node (ref "C61") (pin "2") (pinfunction "2_2") (pintype "passive"))
      (node (ref "C62") (pin "2") (pinfunction "2_2") (pintype "passive"))
      (node (ref "C63") (pin "2") (pinfunction "2_2") (pintype "passive"))
      (node (ref "C64") (pin "2") (pinfunction "2_2") (pintype "passive"))
      (node (ref "C65") (pin "2") (pinfunction "2_2") (pintype "passive"))
      (node (ref "C66") (pin "2") (pinfunction "2_2") (pintype "passive"))
      (node (ref "C67") (pin "2") (pinfunction "2_2") (pintype "passive"))
      (node (ref "C7") (pin "2") (pinfunction "2_2") (pintype "passive"))
      (node (ref "C8") (pin "2") (pinfunction "2_2") (pintype "passive"))
      (node (ref "C9") (pin "2") (pinfunction "2_2") (pintype "passive"))
      (node (ref "IN") (pin "1") (pinfunction "1_1") (pintype "passive"))
      (node (ref "L1") (pin "VSS") (pinfunction "GND_VSS") (pintype "power_in"))
      (node (ref "L10") (pin "VSS") (pinfunction "GND_VSS") (pintype "power_in"))
      (node (ref "L11") (pin "VSS") (pinfunction "GND_VSS") (pintype "power_in"))
      (node (ref "L12") (pin "VSS") (pinfunction "GND_VSS") (pintype "power_in"))
      (node (ref "L13") (pin "VSS") (pinfunction "GND_VSS") (pintype "power_in"))
      (node (ref "L14") (pin "VSS") (pinfunction "GND_VSS") (pintype "power_in"))
      (node (ref "L15") (pin "VSS") (pinfunction "GND_VSS") (pintype "power_in"))
      (node (ref "L16") (pin "VSS") (pinfunction "GND_VSS") (pintype "power_in"))
      (node (ref "L17") (pin "VSS") (pinfunction "GND_VSS") (pintype "power_in"))
      (node (ref "L18") (pin "VSS") (pinfunction "GND_VSS") (pintype "power_in"))
      (node (ref "L19") (pin "VSS") (pinfunction "GND_VSS") (pintype "power_in"))
      (node (ref "L2") (pin "VSS") (pinfunction "GND_VSS") (pintype "power_in"))
      (node (ref "L20") (pin "VSS") (pinfunction "GND_VSS") (pintype "power_in"))
      (node (ref "L21") (pin "VSS") (pinfunction "GND_VSS") (pintype "power_in"))
      (node (ref "L22") (pin "VSS") (pinfunction "GND_VSS") (pintype "power_in"))
      (node (ref "L23") (pin "VSS") (pinfunction "GND_VSS") (pintype "power_in"))
      (node (ref "L24") (pin "VSS") (pinfunction "GND_VSS") (pintype "power_in"))
      (node (ref "L25") (pin "VSS") (pinfunction "GND_VSS") (pintype "power_in"))
      (node (ref "L26") (pin "VSS") (pinfunction "GND_VSS") (pintype "power_in"))
      (node (ref "L27") (pin "VSS") (pinfunction "GND_VSS") (pintype "power_in"))
      (node (ref "L28") (pin "VSS") (pinfunction "GND_VSS") (pintype "power_in"))
      (node (ref "L29") (pin "VSS") (pinfunction "GND_VSS") (pintype "power_in"))
      (node (ref "L3") (pin "VSS") (pinfunction "GND_VSS") (pintype "power_in"))
      (node (ref "L30") (pin "VSS") (pinfunction "GND_VSS") (pintype "power_in"))
      (node (ref "L31") (pin "VSS") (pinfunction "GND_VSS") (pintype "power_in"))
      (node (ref "L32") (pin "VSS") (pinfunction "GND_VSS") (pintype "power_in"))
      (node (ref "L33") (pin "VSS") (pinfunction "GND_VSS") (pintype "power_in"))
      (node (ref "L34") (pin "VSS") (pinfunction "GND_VSS") (pintype "power_in"))
      (node (ref "L35") (pin "VSS") (pinfunction "GND_VSS") (pintype "power_in"))
      (node (ref "L36") (pin "VSS") (pinfunction "GND_VSS") (pintype "power_in"))
      (node (ref "L37") (pin "VSS") (pinfunction "GND_VSS") (pintype "power_in"))
      (node (ref "L38") (pin "VSS") (pinfunction "GND_VSS") (pintype "power_in"))
      (node (ref "L39") (pin "VSS") (pinfunction "GND_VSS") (pintype "power_in"))
      (node (ref "L4") (pin "VSS") (pinfunction "GND_VSS") (pintype "power_in"))
      (node (ref "L40") (pin "VSS") (pinfunction "GND_VSS") (pintype "power_in"))
      (node (ref "L41") (pin "VSS") (pinfunction "GND_VSS") (pintype "power_in"))
      (node (ref "L42") (pin "VSS") (pinfunction "GND_VSS") (pintype "power_in"))
      (node (ref "L43") (pin "VSS") (pinfunction "GND_VSS") (pintype "power_in"))
      (node (ref "L44") (pin "VSS") (pinfunction "GND_VSS") (pintype "power_in"))
      (node (ref "L45") (pin "VSS") (pinfunction "GND_VSS") (pintype "power_in"))
      (node (ref "L46") (pin "VSS") (pinfunction "GND_VSS") (pintype "power_in"))
      (node (ref "L47") (pin "VSS") (pinfunction "GND_VSS") (pintype "power_in"))
      (node (ref "L48") (pin "VSS") (pinfunction "GND_VSS") (pintype "power_in"))
      (node (ref "L49") (pin "VSS") (pinfunction "GND_VSS") (pintype "power_in"))
      (node (ref "L5") (pin "VSS") (pinfunction "GND_VSS") (pintype "power_in"))
      (node (ref "L50") (pin "VSS") (pinfunction "GND_VSS") (pintype "power_in"))
      (node (ref "L51") (pin "VSS") (pinfunction "GND_VSS") (pintype "power_in"))
      (node (ref "L52") (pin "VSS") (pinfunction "GND_VSS") (pintype "power_in"))
      (node (ref "L53") (pin "VSS") (pinfunction "GND_VSS") (pintype "power_in"))
      (node (ref "L54") (pin "VSS") (pinfunction "GND_VSS") (pintype "power_in"))
      (node (ref "L55") (pin "VSS") (pinfunction "GND_VSS") (pintype "power_in"))
      (node (ref "L56") (pin "VSS") (pinfunction "GND_VSS") (pintype "power_in"))
      (node (ref "L57") (pin "VSS") (pinfunction "GND_VSS") (pintype "power_in"))
      (node (ref "L58") (pin "VSS") (pinfunction "GND_VSS") (pintype "power_in"))
      (node (ref "L59") (pin "VSS") (pinfunction "GND_VSS") (pintype "power_in"))
      (node (ref "L6") (pin "VSS") (pinfunction "GND_VSS") (pintype "power_in"))
      (node (ref "L60") (pin "VSS") (pinfunction "GND_VSS") (pintype "power_in"))
      (node (ref "L61") (pin "VSS") (pinfunction "GND_VSS") (pintype "power_in"))
      (node (ref "L62") (pin "VSS") (pinfunction "GND_VSS") (pintype "power_in"))
      (node (ref "L63") (pin "VSS") (pinfunction "GND_VSS") (pintype "power_in"))
      (node (ref "L64") (pin "VSS") (pinfunction "GND_VSS") (pintype "power_in"))
      (node (ref "L65") (pin "VSS") (pinfunction "GND_VSS") (pintype "power_in"))
      (node (ref "L66") (pin "VSS") (pinfunction "GND_VSS") (pintype "power_in"))
      (node (ref "L67") (pin "VSS") (pinfunction "GND_VSS") (pintype "power_in"))
      (node (ref "L68") (pin "VSS") (pinfunction "GND_VSS") (pintype "power_in"))
      (node (ref "L69") (pin "VSS") (pinfunction "GND_VSS") (pintype "power_in"))
      (node (ref "L7") (pin "VSS") (pinfunction "GND_VSS") (pintype "power_in"))
      (node (ref "L70") (pin "VSS") (pinfunction "GND_VSS") (pintype "power_in"))
      (node (ref "L71") (pin "VSS") (pinfunction "GND_VSS") (pintype "power_in"))
      (node (ref "L72") (pin "VSS") (pinfunction "GND_VSS") (pintype "power_in"))
      (node (ref "L73") (pin "VSS") (pinfunction "GND_VSS") (pintype "power_in"))
      (node (ref "L74") (pin "VSS") (pinfunction "GND_VSS") (pintype "power_in"))
      (node (ref "L75") (pin "VSS") (pinfunction "GND_VSS") (pintype "power_in"))
      (node (ref "L76") (pin "VSS") (pinfunction "GND_VSS") (pintype "power_in"))
      (node (ref "L77") (pin "VSS") (pinfunction "GND_VSS") (pintype "power_in"))
      (node (ref "L78") (pin "VSS") (pinfunction "GND_VSS") (pintype "power_in"))
      (node (ref "L79") (pin "VSS") (pinfunction "GND_VSS") (pintype "power_in"))
      (node (ref "L8") (pin "VSS") (pinfunction "GND_VSS") (pintype "power_in"))
      (node (ref "L80") (pin "VSS") (pinfunction "GND_VSS") (pintype "power_in"))
      (node (ref "L81") (pin "VSS") (pinfunction "GND_VSS") (pintype "power_in"))
      (node (ref "L82") (pin "VSS") (pinfunction "GND_VSS") (pintype "power_in"))
      (node (ref "L83") (pin "VSS") (pinfunction "GND_VSS") (pintype "power_in"))
      (node (ref "L84") (pin "VSS") (pinfunction "GND_VSS") (pintype "power_in"))
      (node (ref "L85") (pin "VSS") (pinfunction "GND_VSS") (pintype "power_in"))
      (node (ref "L86") (pin "VSS") (pinfunction "GND_VSS") (pintype "power_in"))
      (node (ref "L87") (pin "VSS") (pinfunction "GND_VSS") (pintype "power_in"))
      (node (ref "L88") (pin "VSS") (pinfunction "GND_VSS") (pintype "power_in"))
      (node (ref "L89") (pin "VSS") (pinfunction "GND_VSS") (pintype "power_in"))
      (node (ref "L9") (pin "VSS") (pinfunction "GND_VSS") (pintype "power_in"))
      (node (ref "L90") (pin "VSS") (pinfunction "GND_VSS") (pintype "power_in"))
      (node (ref "L91") (pin "VSS") (pinfunction "GND_VSS") (pintype "power_in"))
      (node (ref "L92") (pin "VSS") (pinfunction "GND_VSS") (pintype "power_in"))
      (node (ref "L93") (pin "VSS") (pinfunction "GND_VSS") (pintype "power_in"))
      (node (ref "L94") (pin "VSS") (pinfunction "GND_VSS") (pintype "power_in"))
      (node (ref "L95") (pin "VSS") (pinfunction "GND_VSS") (pintype "power_in"))
      (node (ref "L96") (pin "VSS") (pinfunction "GND_VSS") (pintype "power_in"))
    )
    (net (code "4") (name "Net-(L1-DO)") (class "Default")
      (node (ref "L1") (pin "DOUT") (pinfunction "DO_DOUT") (pintype "output"))
      (node (ref "L2") (pin "DIN") (pinfunction "DI_DIN") (pintype "input"))
    )
    (net (code "5") (name "Net-(L2-DO)") (class "Default")
      (node (ref "L2") (pin "DOUT") (pinfunction "DO_DOUT") (pintype "output"))
      (node (ref "L3") (pin "DIN") (pinfunction "DI_DIN") (pintype "input"))
    )
    (net (code "6") (name "Net-(L3-DO)") (class "Default")
      (node (ref "L3") (pin "DOUT") (pinfunction "DO_DOUT") (pintype "output"))
      (node (ref "L4") (pin "DIN") (pinfunction "DI_DIN") (pintype "input"))
    )
    (net (code "7") (name "Net-(L4-DO)") (class "Default")
      (node (ref "L4") (pin "DOUT") (pinfunction "DO_DOUT") (pintype "output"))
      (node (ref "L5") (pin "DIN") (pinfunction "DI_DIN") (pintype "input"))
    )
    (net (code "8") (name "Net-(L5-DO)") (class "Default")
      (node (ref "L5") (pin "DOUT") (pinfunction "DO_DOUT") (pintype "output"))
      (node (ref "L6") (pin "DIN") (pinfunction "DI_DIN") (pintype "input"))
    )
    (net (code "9") (name "Net-(L6-DO)") (class "Default")
      (node (ref "L6") (pin "DOUT") (pinfunction "DO_DOUT") (pintype "output"))
      (node (ref "L7") (pin "DIN") (pinfunction "DI_DIN") (pintype "input"))
    )
    (net (code "10") (name "Net-(L7-DO)") (class "Default")
      (node (ref "L7") (pin "DOUT") (pinfunction "DO_DOUT") (pintype "output"))
      (node (ref "L8") (pin "DIN") (pinfunction "DI_DIN") (pintype "input"))
    )
    (net (code "11") (name "Net-(L8-DO)") (class "Default")
      (node (ref "L8") (pin "DOUT") (pinfunction "DO_DOUT") (pintype "output"))
      (node (ref "L9") (pin "DIN") (pinfunction "DI_DIN") (pintype "input"))
    )
    (net (code "12") (name "Net-(L10-DI)") (class "Default")
      (node (ref "L10") (pin "DIN") (pinfunction "DI_DIN") (pintype "input"))
      (node (ref "L9") (pin "DOUT") (pinfunction "DO_DOUT") (pintype "output"))
    )
    (net (code "13") (name "Net-(L10-DO)") (class "Default")
      (node (ref "L10") (pin "DOUT") (pinfunction "DO_DOUT") (pintype "output"))
      (node (ref "L11") (pin "DIN") (pinfunction "DI_DIN") (pintype "input"))
    )
    (net (code "14") (name "Net-(L11-DO)") (class "Default")
      (node (ref "L11") (pin "DOUT") (pinfunction "DO_DOUT") (pintype "output"))
      (node (ref "L12") (pin "DIN") (pinfunction "DI_DIN") (pintype "input"))
    )
    (net (code "15") (name "Net-(L12-DO)") (class "Default")
      (node (ref "L12") (pin "DOUT") (pinfunction "DO_DOUT") (pintype "output"))
      (node (ref "L13") (pin "DIN") (pinfunction "DI_DIN") (pintype "input"))
    )
    (net (code "16") (name "Net-(L13-DO)") (class "Default")
      (node (ref "L13") (pin "DOUT") (pinfunction "DO_DOUT") (pintype "output"))
      (node (ref "L14") (pin "DIN") (pinfunction "DI_DIN") (pintype "input"))
    )
    (net (code "17") (name "Net-(L14-DO)") (class "Default")
      (node (ref "L14") (pin "DOUT") (pinfunction "DO_DOUT") (pintype "output"))
      (node (ref "L15") (pin "DIN") (pinfunction "DI_DIN") (pintype "input"))
    )
    (net (code "18") (name "Net-(L15-DO)") (class "Default")
      (node (ref "L15") (pin "DOUT") (pinfunction "DO_DOUT") (pintype "output"))
      (node (ref "L16") (pin "DIN") (pinfunction "DI_DIN") (pintype "input"))
    )
    (net (code "19") (name "Net-(L16-DO)") (class "Default")
      (node (ref "L16") (pin "DOUT") (pinfunction "DO_DOUT") (pintype "output"))
      (node (ref "L32") (pin "DIN") (pinfunction "DI_DIN") (pintype "input"))
    )
    (net (code "20") (name "Net-(L17-DI)") (class "Default")
      (node (ref "L17") (pin "DIN") (pinfunction "DI_DIN") (pintype "input"))
      (node (ref "L18") (pin "DOUT") (pinfunction "DO_DOUT") (pintype "output"))
    )
    (net (code "21") (name "Net-(L17-DO)") (class "Default")
      (node (ref "L17") (pin "DOUT") (pinfunction "DO_DOUT") (pintype "output"))
      (node (ref "L33") (pin "DIN") (pinfunction "DI_DIN") (pintype "input"))
    )
    (net (code "22") (name "Net-(L18-DI)") (class "Default")
      (node (ref "L18") (pin "DIN") (pinfunction "DI_DIN") (pintype "input"))
      (node (ref "L19") (pin "DOUT") (pinfunction "DO_DOUT") (pintype "output"))
    )
    (net (code "23") (name "Net-(L19-DI)") (class "Default")
      (node (ref "L19") (pin "DIN") (pinfunction "DI_DIN") (pintype "input"))
      (node (ref "L20") (pin "DOUT") (pinfunction "DO_DOUT") (pintype "output"))
    )
    (net (code "24") (name "Net-(L20-DI)") (class "Default")
      (node (ref "L20") (pin "DIN") (pinfunction "DI_DIN") (pintype "input"))
      (node (ref "L21") (pin "DOUT") (pinfunction "DO_DOUT") (pintype "output"))
    )
    (net (code "25") (name "Net-(L21-DI)") (class "Default")
      (node (ref "L21") (pin "DIN") (pinfunction "DI_DIN") (pintype "input"))
      (node (ref "L22") (pin "DOUT") (pinfunction "DO_DOUT") (pintype "output"))
    )
    (net (code "26") (name "Net-(L22-DI)") (class "Default")
      (node (ref "L22") (pin "DIN") (pinfunction "DI_DIN") (pintype "input"))
      (node (ref "L23") (pin "DOUT") (pinfunction "DO_DOUT") (pintype "output"))
    )
    (net (code "27") (name "Net-(L23-DI)") (class "Default")
      (node (ref "L23") (pin "DIN") (pinfunction "DI_DIN") (pintype "input"))
      (node (ref "L24") (pin "DOUT") (pinfunction "DO_DOUT") (pintype "output"))
    )
    (net (code "28") (name "Net-(L24-DI)") (class "Default")
      (node (ref "L24") (pin "DIN") (pinfunction "DI_DIN") (pintype "input"))
      (node (ref "L25") (pin "DOUT") (pinfunction "DO_DOUT") (pintype "output"))
    )
    (net (code "29") (name "Net-(L25-DI)") (class "Default")
      (node (ref "L25") (pin "DIN") (pinfunction "DI_DIN") (pintype "input"))
      (node (ref "L26") (pin "DOUT") (pinfunction "DO_DOUT") (pintype "output"))
    )
    (net (code "30") (name "Net-(L26-DI)") (class "Default")
      (node (ref "L26") (pin "DIN") (pinfunction "DI_DIN") (pintype "input"))
      (node (ref "L27") (pin "DOUT") (pinfunction "DO_DOUT") (pintype "output"))
    )
    (net (code "31") (name "Net-(L27-DI)") (class "Default")
      (node (ref "L27") (pin "DIN") (pinfunction "DI_DIN") (pintype "input"))
      (node (ref "L28") (pin "DOUT") (pinfunction "DO_DOUT") (pintype "output"))
    )
    (net (code "32") (name "Net-(L28-DI)") (class "Default")
      (node (ref "L28") (pin "DIN") (pinfunction "DI_DIN") (pintype "input"))
      (node (ref "L29") (pin "DOUT") (pinfunction "DO_DOUT") (pintype "output"))
    )
    (net (code "33") (name "Net-(L29-DI)") (class "Default")
      (node (ref "L29") (pin "DIN") (pinfunction "DI_DIN") (pintype "input"))
      (node (ref "L30") (pin "DOUT") (pinfunction "DO_DOUT") (pintype "output"))
    )
    (net (code "34") (name "Net-(L30-DI)") (class "Default")
      (node (ref "L30") (pin "DIN") (pinfunction "DI_DIN") (pintype "input"))
      (node (ref "L31") (pin "DOUT") (pinfunction "DO_DOUT") (pintype "output"))
    )
    (net (code "35") (name "Net-(L31-DI)") (class "Default")
      (node (ref "L31") (pin "DIN") (pinfunction "DI_DIN") (pintype "input"))
      (node (ref "L32") (pin "DOUT") (pinfunction "DO_DOUT") (pintype "output"))
    )
    (net (code "36") (name "Net-(L33-DO)") (class "Default")
      (node (ref "L33") (pin "DOUT") (pinfunction "DO_DOUT") (pintype "output"))
      (node (ref "L34") (pin "DIN") (pinfunction "DI_DIN") (pintype "input"))
    )
    (net (code "37") (name "Net-(L34-DO)") (class "Default")
      (node (ref "L34") (pin "DOUT") (pinfunction "DO_DOUT") (pintype "output"))
      (node (ref "L35") (pin "DIN") (pinfunction "DI_DIN") (pintype "input"))
    )
    (net (code "38") (name "Net-(L35-DO)") (class "Default")
      (node (ref "L35") (pin "DOUT") (pinfunction "DO_DOUT") (pintype "output"))
      (node (ref "L36") (pin "DIN") (pinfunction "DI_DIN") (pintype "input"))
    )
    (net (code "39") (name "Net-(L36-DO)") (class "Default")
      (node (ref "L36") (pin "DOUT") (pinfunction "DO_DOUT") (pintype "output"))
      (node (ref "L37") (pin "DIN") (pinfunction "DI_DIN") (pintype "input"))
    )
    (net (code "40") (name "Net-(L37-DO)") (class "Default")
      (node (ref "L37") (pin "DOUT") (pinfunction "DO_DOUT") (pintype "output"))
      (node (ref "L38") (pin "DIN") (pinfunction "DI_DIN") (pintype "input"))
    )
    (net (code "41") (name "Net-(L38-DO)") (class "Default")
      (node (ref "L38") (pin "DOUT") (pinfunction "DO_DOUT") (pintype "output"))
      (node (ref "L39") (pin "DIN") (pinfunction "DI_DIN") (pintype "input"))
    )
    (net (code "42") (name "Net-(L39-DO)") (class "Default")
      (node (ref "L39") (pin "DOUT") (pinfunction "DO_DOUT") (pintype "output"))
      (node (ref "L40") (pin "DIN") (pinfunction "DI_DIN") (pintype "input"))
    )
    (net (code "43") (name "Net-(L40-DO)") (class "Default")
      (node (ref "L40") (pin "DOUT") (pinfunction "DO_DOUT") (pintype "output"))
      (node (ref "L41") (pin "DIN") (pinfunction "DI_DIN") (pintype "input"))
    )
    (net (code "44") (name "Net-(L41-DO)") (class "Default")
      (node (ref "L41") (pin "DOUT") (pinfunction "DO_DOUT") (pintype "output"))
      (node (ref "L42") (pin "DIN") (pinfunction "DI_DIN") (pintype "input"))
    )
    (net (code "45") (name "Net-(L42-DO)") (class "Default")
      (node (ref "L42") (pin "DOUT") (pinfunction "DO_DOUT") (pintype "output"))
      (node (ref "L43") (pin "DIN") (pinfunction "DI_DIN") (pintype "input"))
    )
    (net (code "46") (name "Net-(L43-DO)") (class "Default")
      (node (ref "L43") (pin "DOUT") (pinfunction "DO_DOUT") (pintype "output"))
      (node (ref "L44") (pin "DIN") (pinfunction "DI_DIN") (pintype "input"))
    )
    (net (code "47") (name "Net-(L44-DO)") (class "Default")
      (node (ref "L44") (pin "DOUT") (pinfunction "DO_DOUT") (pintype "output"))
      (node (ref "L45") (pin "DIN") (pinfunction "DI_DIN") (pintype "input"))
    )
    (net (code "48") (name "Net-(L45-DO)") (class "Default")
      (node (ref "L45") (pin "DOUT") (pinfunction "DO_DOUT") (pintype "output"))
      (node (ref "L46") (pin "DIN") (pinfunction "DI_DIN") (pintype "input"))
    )
    (net (code "49") (name "Net-(L46-DO)") (class "Default")
      (node (ref "L46") (pin "DOUT") (pinfunction "DO_DOUT") (pintype "output"))
      (node (ref "L47") (pin "DIN") (pinfunction "DI_DIN") (pintype "input"))
    )
    (net (code "50") (name "Net-(L47-DO)") (class "Default")
      (node (ref "L47") (pin "DOUT") (pinfunction "DO_DOUT") (pintype "output"))
      (node (ref "L48") (pin "DIN") (pinfunction "DI_DIN") (pintype "input"))
    )
    (net (code "51") (name "Net-(L48-DO)") (class "Default")
      (node (ref "L48") (pin "DOUT") (pinfunction "DO_DOUT") (pintype "output"))
      (node (ref "L64") (pin "DIN") (pinfunction "DI_DIN") (pintype "input"))
    )
    (net (code "52") (name "Net-(L49-DI)") (class "Default")
      (node (ref "L49") (pin "DIN") (pinfunction "DI_DIN") (pintype "input"))
      (node (ref "L50") (pin "DOUT") (pinfunction "DO_DOUT") (pintype "output"))
    )
    (net (code "53") (name "Net-(L49-DO)") (class "Default")
      (node (ref "L49") (pin "DOUT") (pinfunction "DO_DOUT") (pintype "output"))
      (node (ref "L65") (pin "DIN") (pinfunction "DI_DIN") (pintype "input"))
    )
    (net (code "54") (name "Net-(L50-DI)") (class "Default")
      (node (ref "L50") (pin "DIN") (pinfunction "DI_DIN") (pintype "input"))
      (node (ref "L51") (pin "DOUT") (pinfunction "DO_DOUT") (pintype "output"))
    )
    (net (code "55") (name "Net-(L51-DI)") (class "Default")
      (node (ref "L51") (pin "DIN") (pinfunction "DI_DIN") (pintype "input"))
      (node (ref "L52") (pin "DOUT") (pinfunction "DO_DOUT") (pintype "output"))
    )
    (net (code "56") (name "Net-(L52-DI)") (class "Default")
      (node (ref "L52") (pin "DIN") (pinfunction "DI_DIN") (pintype "input"))
      (node (ref "L53") (pin "DOUT") (pinfunction "DO_DOUT") (pintype "output"))
    )
    (net (code "57") (name "Net-(L53-DI)") (class "Default")
      (node (ref "L53") (pin "DIN") (pinfunction "DI_DIN") (pintype "input"))
      (node (ref "L54") (pin "DOUT") (pinfunction "DO_DOUT") (pintype "output"))
    )
    (net (code "58") (name "Net-(L54-DI)") (class "Default")
      (node (ref "L54") (pin "DIN") (pinfunction "DI_DIN") (pintype "input"))
      (node (ref "L55") (pin "DOUT") (pinfunction "DO_DOUT") (pintype "output"))
    )
    (net (code "59") (name "Net-(L55-DI)") (class "Default")
      (node (ref "L55") (pin "DIN") (pinfunction "DI_DIN") (pintype "input"))
      (node (ref "L56") (pin "DOUT") (pinfunction "DO_DOUT") (pintype "output"))
    )
    (net (code "60") (name "Net-(L56-DI)") (class "Default")
      (node (ref "L56") (pin "DIN") (pinfunction "DI_DIN") (pintype "input"))
      (node (ref "L57") (pin "DOUT") (pinfunction "DO_DOUT") (pintype "output"))
    )
    (net (code "61") (name "Net-(L57-DI)") (class "Default")
      (node (ref "L57") (pin "DIN") (pinfunction "DI_DIN") (pintype "input"))
      (node (ref "L58") (pin "DOUT") (pinfunction "DO_DOUT") (pintype "output"))
    )
    (net (code "62") (name "Net-(L58-DI)") (class "Default")
      (node (ref "L58") (pin "DIN") (pinfunction "DI_DIN") (pintype "input"))
      (node (ref "L59") (pin "DOUT") (pinfunction "DO_DOUT") (pintype "output"))
    )
    (net (code "63") (name "Net-(L59-DI)") (class "Default")
      (node (ref "L59") (pin "DIN") (pinfunction "DI_DIN") (pintype "input"))
      (node (ref "L60") (pin "DOUT") (pinfunction "DO_DOUT") (pintype "output"))
    )
    (net (code "64") (name "Net-(L60-DI)") (class "Default")
      (node (ref "L60") (pin "DIN") (pinfunction "DI_DIN") (pintype "input"))
      (node (ref "L61") (pin "DOUT") (pinfunction "DO_DOUT") (pintype "output"))
    )
    (net (code "65") (name "Net-(L61-DI)") (class "Default")
      (node (ref "L61") (pin "DIN") (pinfunction "DI_DIN") (pintype "input"))
      (node (ref "L62") (pin "DOUT") (pinfunction "DO_DOUT") (pintype "output"))
    )
    (net (code "66") (name "Net-(L62-DI)") (class "Default")
      (node (ref "L62") (pin "DIN") (pinfunction "DI_DIN") (pintype "input"))
      (node (ref "L63") (pin "DOUT") (pinfunction "DO_DOUT") (pintype "output"))
    )
    (net (code "67") (name "Net-(L63-DI)") (class "Default")
      (node (ref "L63") (pin "DIN") (pinfunction "DI_DIN") (pintype "input"))
      (node (ref "L64") (pin "DOUT") (pinfunction "DO_DOUT") (pintype "output"))
    )
    (net (code "68") (name "Net-(L65-DO)") (class "Default")
      (node (ref "L65") (pin "DOUT") (pinfunction "DO_DOUT") (pintype "output"))
      (node (ref "L66") (pin "DIN") (pinfunction "DI_DIN") (pintype "input"))
    )
    (net (code "69") (name "Net-(L66-DO)") (class "Default")
      (node (ref "L66") (pin "DOUT") (pinfunction "DO_DOUT") (pintype "output"))
      (node (ref "L67") (pin "DIN") (pinfunction "DI_DIN") (pintype "input"))
    )
    (net (code "70") (name "Net-(L67-DO)") (class "Default")
      (node (ref "L67") (pin "DOUT") (pinfunction "DO_DOUT") (pintype "output"))
      (node (ref "L68") (pin "DIN") (pinfunction "DI_DIN") (pintype "input"))
    )
    (net (code "71") (name "Net-(L68-DO)") (class "Default")
      (node (ref "L68") (pin "DOUT") (pinfunction "DO_DOUT") (pintype "output"))
      (node (ref "L69") (pin "DIN") (pinfunction "DI_DIN") (pintype "input"))
    )
    (net (code "72") (name "Net-(L69-DO)") (class "Default")
      (node (ref "L69") (pin "DOUT") (pinfunction "DO_DOUT") (pintype "output"))
      (node (ref "L70") (pin "DIN") (pinfunction "DI_DIN") (pintype "input"))
    )
    (net (code "73") (name "Net-(L70-DO)") (class "Default")
      (node (ref "L70") (pin "DOUT") (pinfunction "DO_DOUT") (pintype "output"))
      (node (ref "L71") (pin "DIN") (pinfunction "DI_DIN") (pintype "input"))
    )
    (net (code "74") (name "Net-(L71-DO)") (class "Default")
      (node (ref "L71") (pin "DOUT") (pinfunction "DO_DOUT") (pintype "output"))
      (node (ref "L72") (pin "DIN") (pinfunction "DI_DIN") (pintype "input"))
    )
    (net (code "75") (name "Net-(L72-DO)") (class "Default")
      (node (ref "L72") (pin "DOUT") (pinfunction "DO_DOUT") (pintype "output"))
      (node (ref "L73") (pin "DIN") (pinfunction "DI_DIN") (pintype "input"))
    )
    (net (code "76") (name "Net-(L73-DO)") (class "Default")
      (node (ref "L73") (pin "DOUT") (pinfunction "DO_DOUT") (pintype "output"))
      (node (ref "L74") (pin "DIN") (pinfunction "DI_DIN") (pintype "input"))
    )
    (net (code "77") (name "Net-(L74-DO)") (class "Default")
      (node (ref "L74") (pin "DOUT") (pinfunction "DO_DOUT") (pintype "output"))
      (node (ref "L75") (pin "DIN") (pinfunction "DI_DIN") (pintype "input"))
    )
    (net (code "78") (name "Net-(L75-DO)") (class "Default")
      (node (ref "L75") (pin "DOUT") (pinfunction "DO_DOUT") (pintype "output"))
      (node (ref "L76") (pin "DIN") (pinfunction "DI_DIN") (pintype "input"))
    )
    (net (code "79") (name "Net-(L76-DO)") (class "Default")
      (node (ref "L76") (pin "DOUT") (pinfunction "DO_DOUT") (pintype "output"))
      (node (ref "L77") (pin "DIN") (pinfunction "DI_DIN") (pintype "input"))
    )
    (net (code "80") (name "Net-(L77-DO)") (class "Default")
      (node (ref "L77") (pin "DOUT") (pinfunction "DO_DOUT") (pintype "output"))
      (node (ref "L78") (pin "DIN") (pinfunction "DI_DIN") (pintype "input"))
    )
    (net (code "81") (name "Net-(L78-DO)") (class "Default")
      (node (ref "L78") (pin "DOUT") (pinfunction "DO_DOUT") (pintype "output"))
      (node (ref "L79") (pin "DIN") (pinfunction "DI_DIN") (pintype "input"))
    )
    (net (code "82") (name "Net-(L79-DO)") (class "Default")
      (node (ref "L79") (pin "DOUT") (pinfunction "DO_DOUT") (pintype "output"))
      (node (ref "L80") (pin "DIN") (pinfunction "DI_DIN") (pintype "input"))
    )
    (net (code "83") (name "Net-(L80-DO)") (class "Default")
      (node (ref "L80") (pin "DOUT") (pinfunction "DO_DOUT") (pintype "output"))
      (node (ref "L96") (pin "DIN") (pinfunction "DI_DIN") (pintype "input"))
    )
    (net (code "84") (name "Net-(L81-DI)") (class "Default")
      (node (ref "L81") (pin "DIN") (pinfunction "DI_DIN") (pintype "input"))
      (node (ref "L82") (pin "DOUT") (pinfunction "DO_DOUT") (pintype "output"))
    )
    (net (code "85") (name "Net-(L82-DI)") (class "Default")
      (node (ref "L82") (pin "DIN") (pinfunction "DI_DIN") (pintype "input"))
      (node (ref "L83") (pin "DOUT") (pinfunction "DO_DOUT") (pintype "output"))
    )
    (net (code "86") (name "Net-(L83-DI)") (class "Default")
      (node (ref "L83") (pin "DIN") (pinfunction "DI_DIN") (pintype "input"))
      (node (ref "L84") (pin "DOUT") (pinfunction "DO_DOUT") (pintype "output"))
    )
    (net (code "87") (name "Net-(L84-DI)") (class "Default")
      (node (ref "L84") (pin "DIN") (pinfunction "DI_DIN") (pintype "input"))
      (node (ref "L85") (pin "DOUT") (pinfunction "DO_DOUT") (pintype "output"))
    )
    (net (code "88") (name "Net-(L85-DI)") (class "Default")
      (node (ref "L85") (pin "DIN") (pinfunction "DI_DIN") (pintype "input"))
      (node (ref "L86") (pin "DOUT") (pinfunction "DO_DOUT") (pintype "output"))
    )
    (net (code "89") (name "Net-(L86-DI)") (class "Default")
      (node (ref "L86") (pin "DIN") (pinfunction "DI_DIN") (pintype "input"))
      (node (ref "L87") (pin "DOUT") (pinfunction "DO_DOUT") (pintype "output"))
    )
    (net (code "90") (name "Net-(L87-DI)") (class "Default")
      (node (ref "L87") (pin "DIN") (pinfunction "DI_DIN") (pintype "input"))
      (node (ref "L88") (pin "DOUT") (pinfunction "DO_DOUT") (pintype "output"))
    )
    (net (code "91") (name "Net-(L88-DI)") (class "Default")
      (node (ref "L88") (pin "DIN") (pinfunction "DI_DIN") (pintype "input"))
      (node (ref "L89") (pin "DOUT") (pinfunction "DO_DOUT") (pintype "output"))
    )
    (net (code "92") (name "Net-(L89-DI)") (class "Default")
      (node (ref "L89") (pin "DIN") (pinfunction "DI_DIN") (pintype "input"))
      (node (ref "L90") (pin "DOUT") (pinfunction "DO_DOUT") (pintype "output"))
    )
    (net (code "93") (name "Net-(L90-DI)") (class "Default")
      (node (ref "L90") (pin "DIN") (pinfunction "DI_DIN") (pintype "input"))
      (node (ref "L91") (pin "DOUT") (pinfunction "DO_DOUT") (pintype "output"))
    )
    (net (code "94") (name "Net-(L91-DI)") (class "Default")
      (node (ref "L91") (pin "DIN") (pinfunction "DI_DIN") (pintype "input"))
      (node (ref "L92") (pin "DOUT") (pinfunction "DO_DOUT") (pintype "output"))
    )
    (net (code "95") (name "Net-(L92-DI)") (class "Default")
      (node (ref "L92") (pin "DIN") (pinfunction "DI_DIN") (pintype "input"))
      (node (ref "L93") (pin "DOUT") (pinfunction "DO_DOUT") (pintype "output"))
    )
    (net (code "96") (name "Net-(L93-DI)") (class "Default")
      (node (ref "L93") (pin "DIN") (pinfunction "DI_DIN") (pintype "input"))
      (node (ref "L94") (pin "DOUT") (pinfunction "DO_DOUT") (pintype "output"))
    )
    (net (code "97") (name "Net-(L94-DI)") (class "Default")
      (node (ref "L94") (pin "DIN") (pinfunction "DI_DIN") (pintype "input"))
      (node (ref "L95") (pin "DOUT") (pinfunction "DO_DOUT") (pintype "output"))
    )
    (net (code "98") (name "Net-(L95-DI)") (class "Default")
      (node (ref "L95") (pin "DIN") (pinfunction "DI_DIN") (pintype "input"))
      (node (ref "L96") (pin "DOUT") (pinfunction "DO_DOUT") (pintype "output"))
    )
    (net (code "99") (name "unconnected-(L81-DO-PadDOUT)") (class "Default")
      (node (ref "L81") (pin "DOUT") (pinfunction "DO_DOUT") (pintype "output"))
    )
  )
)
